# MegaGRRLDesktop.net
KiCad netlist of a schematic drawn in EAGLE
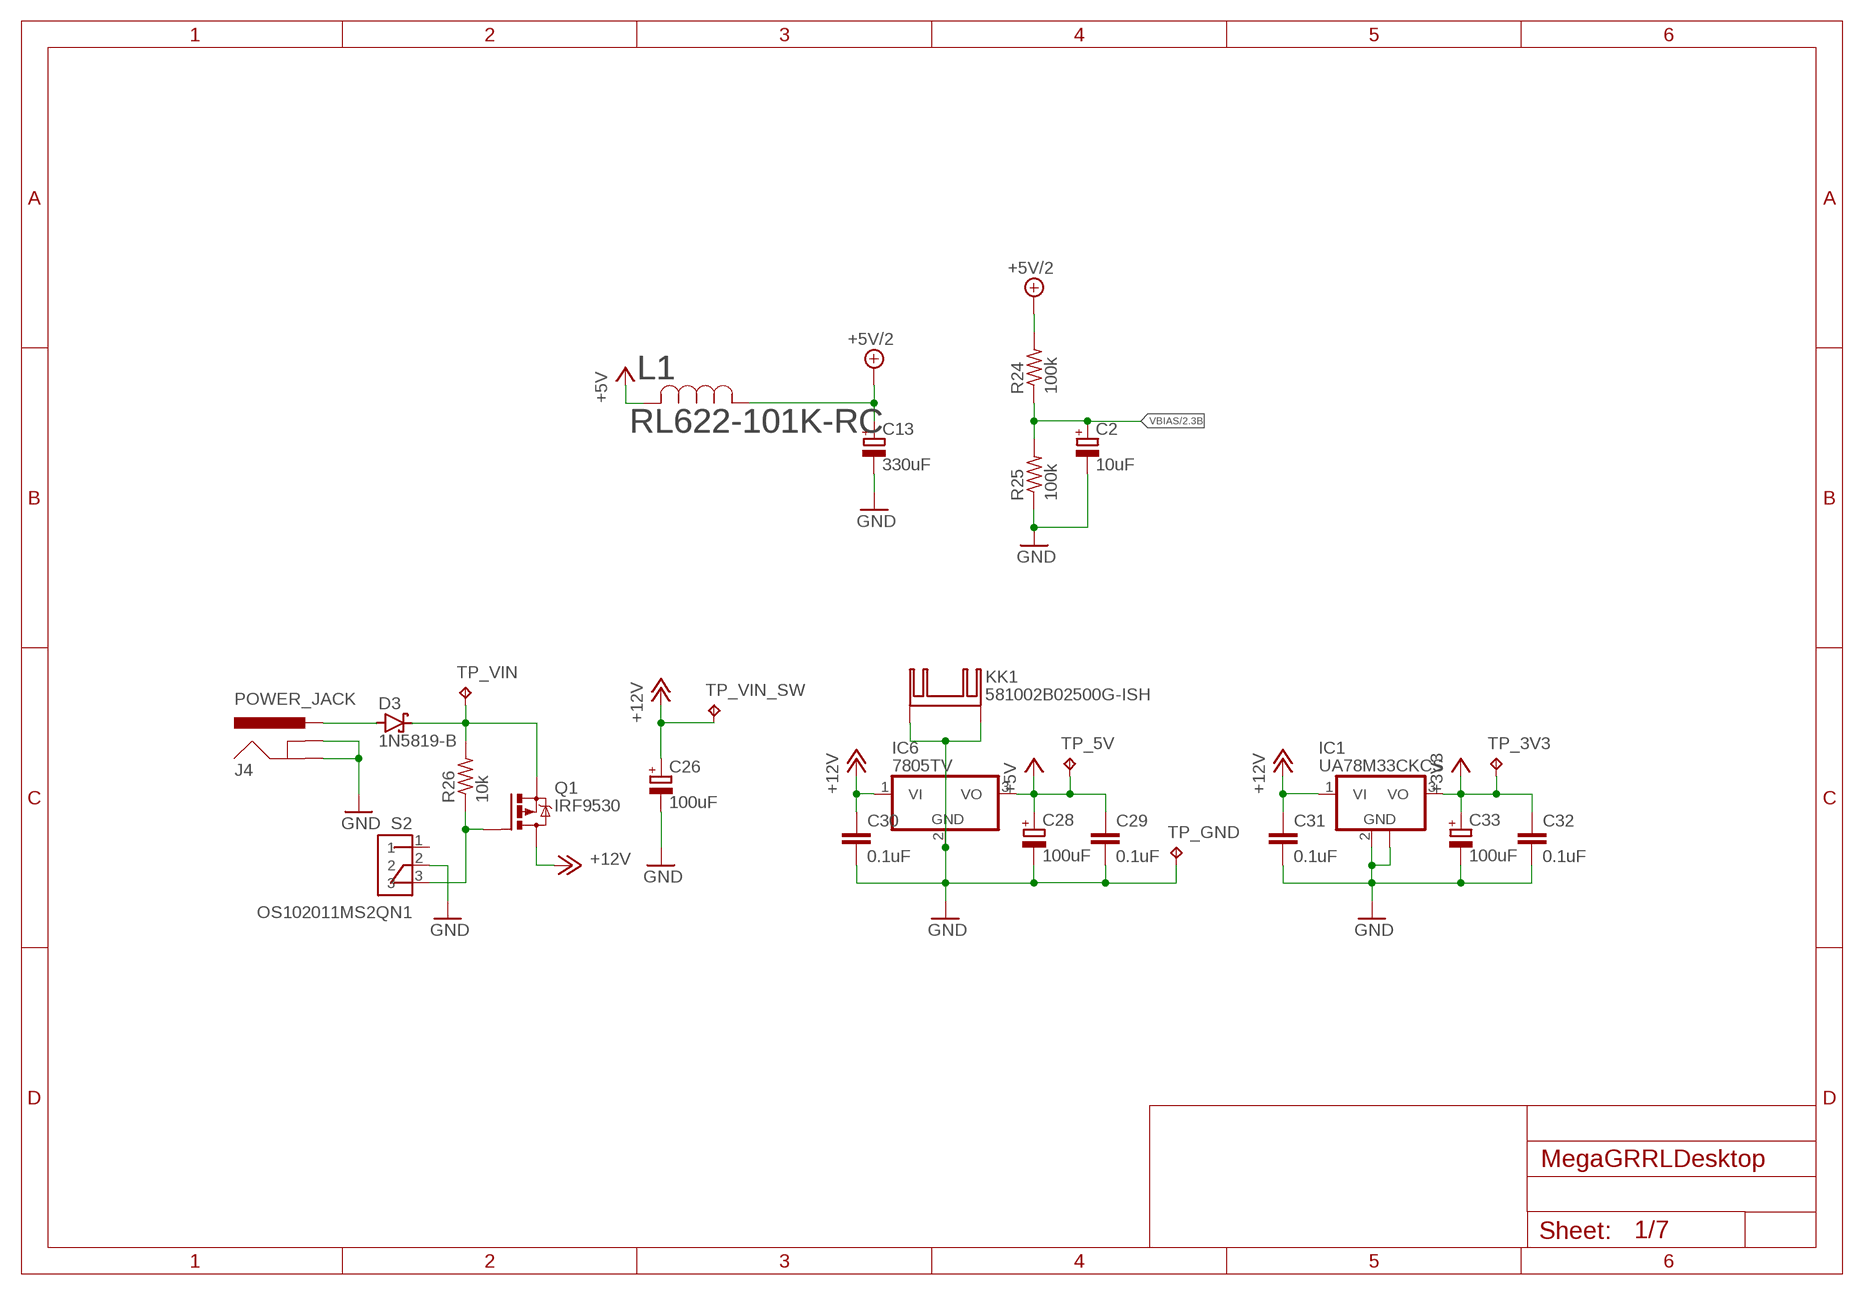
[diagram p0: schematic, sheet 1]
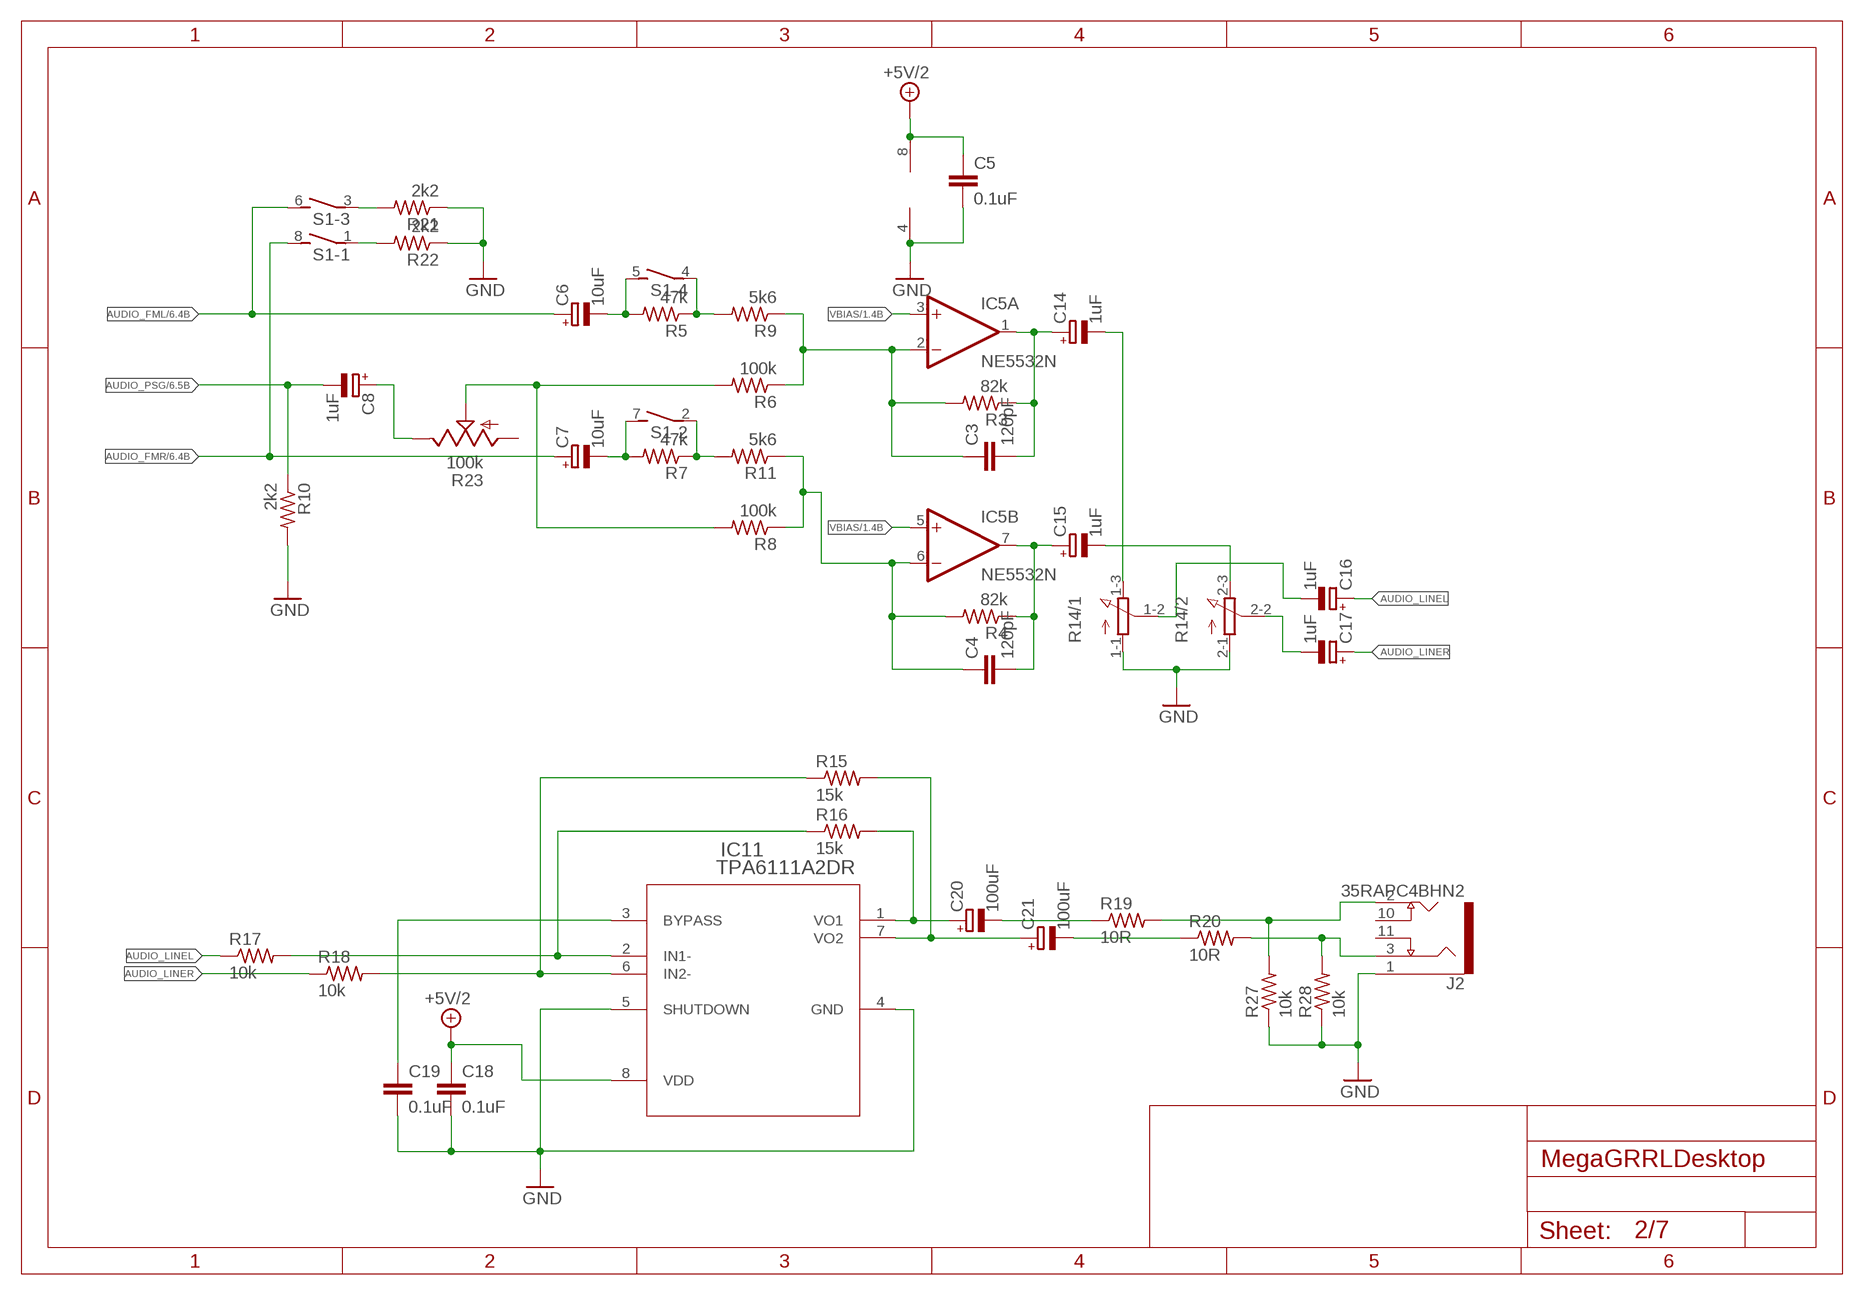
[diagram p1: schematic, sheet 2]
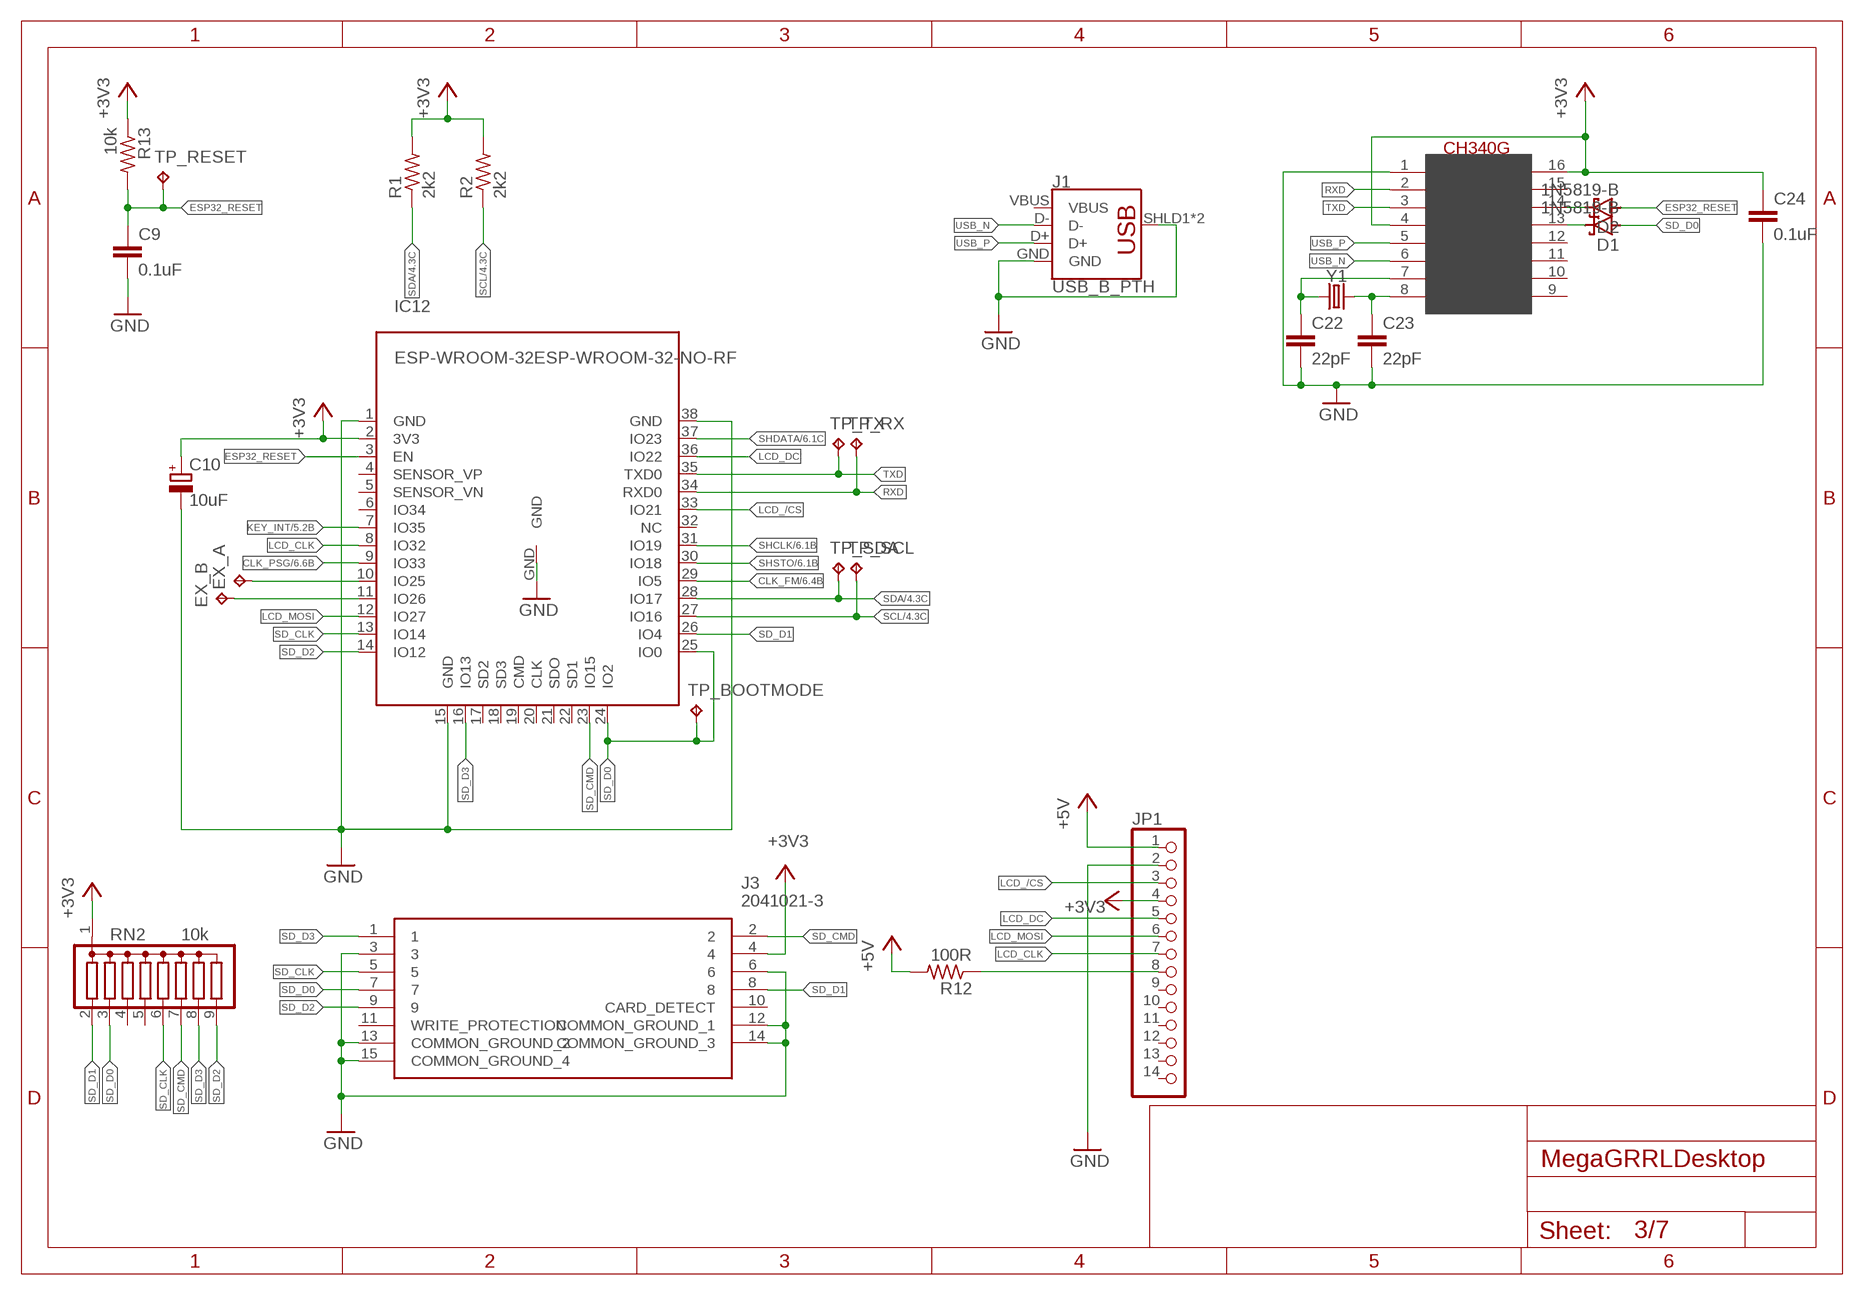
[diagram p2: schematic, sheet 3]
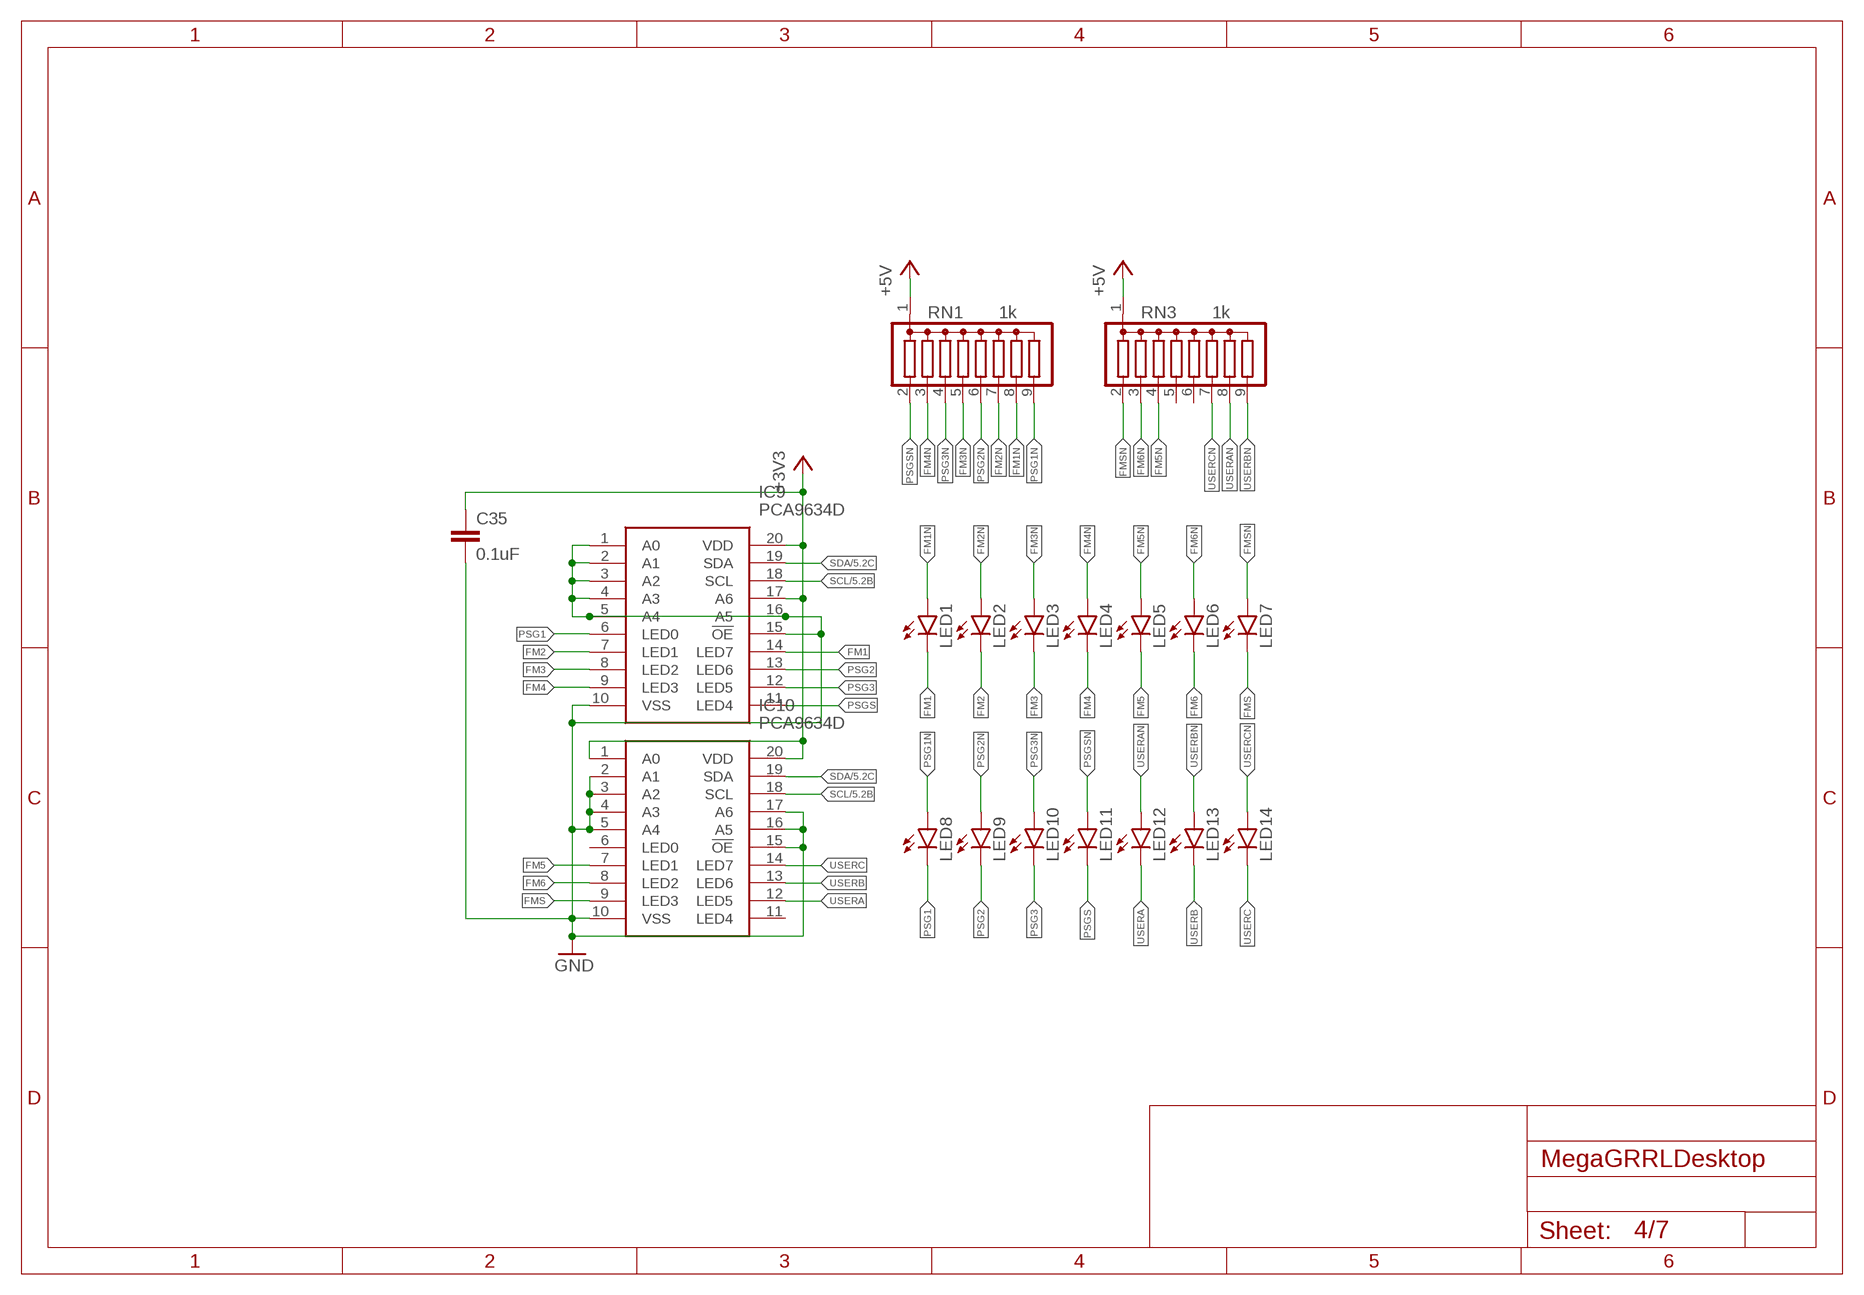
[diagram p3: schematic, sheet 4]
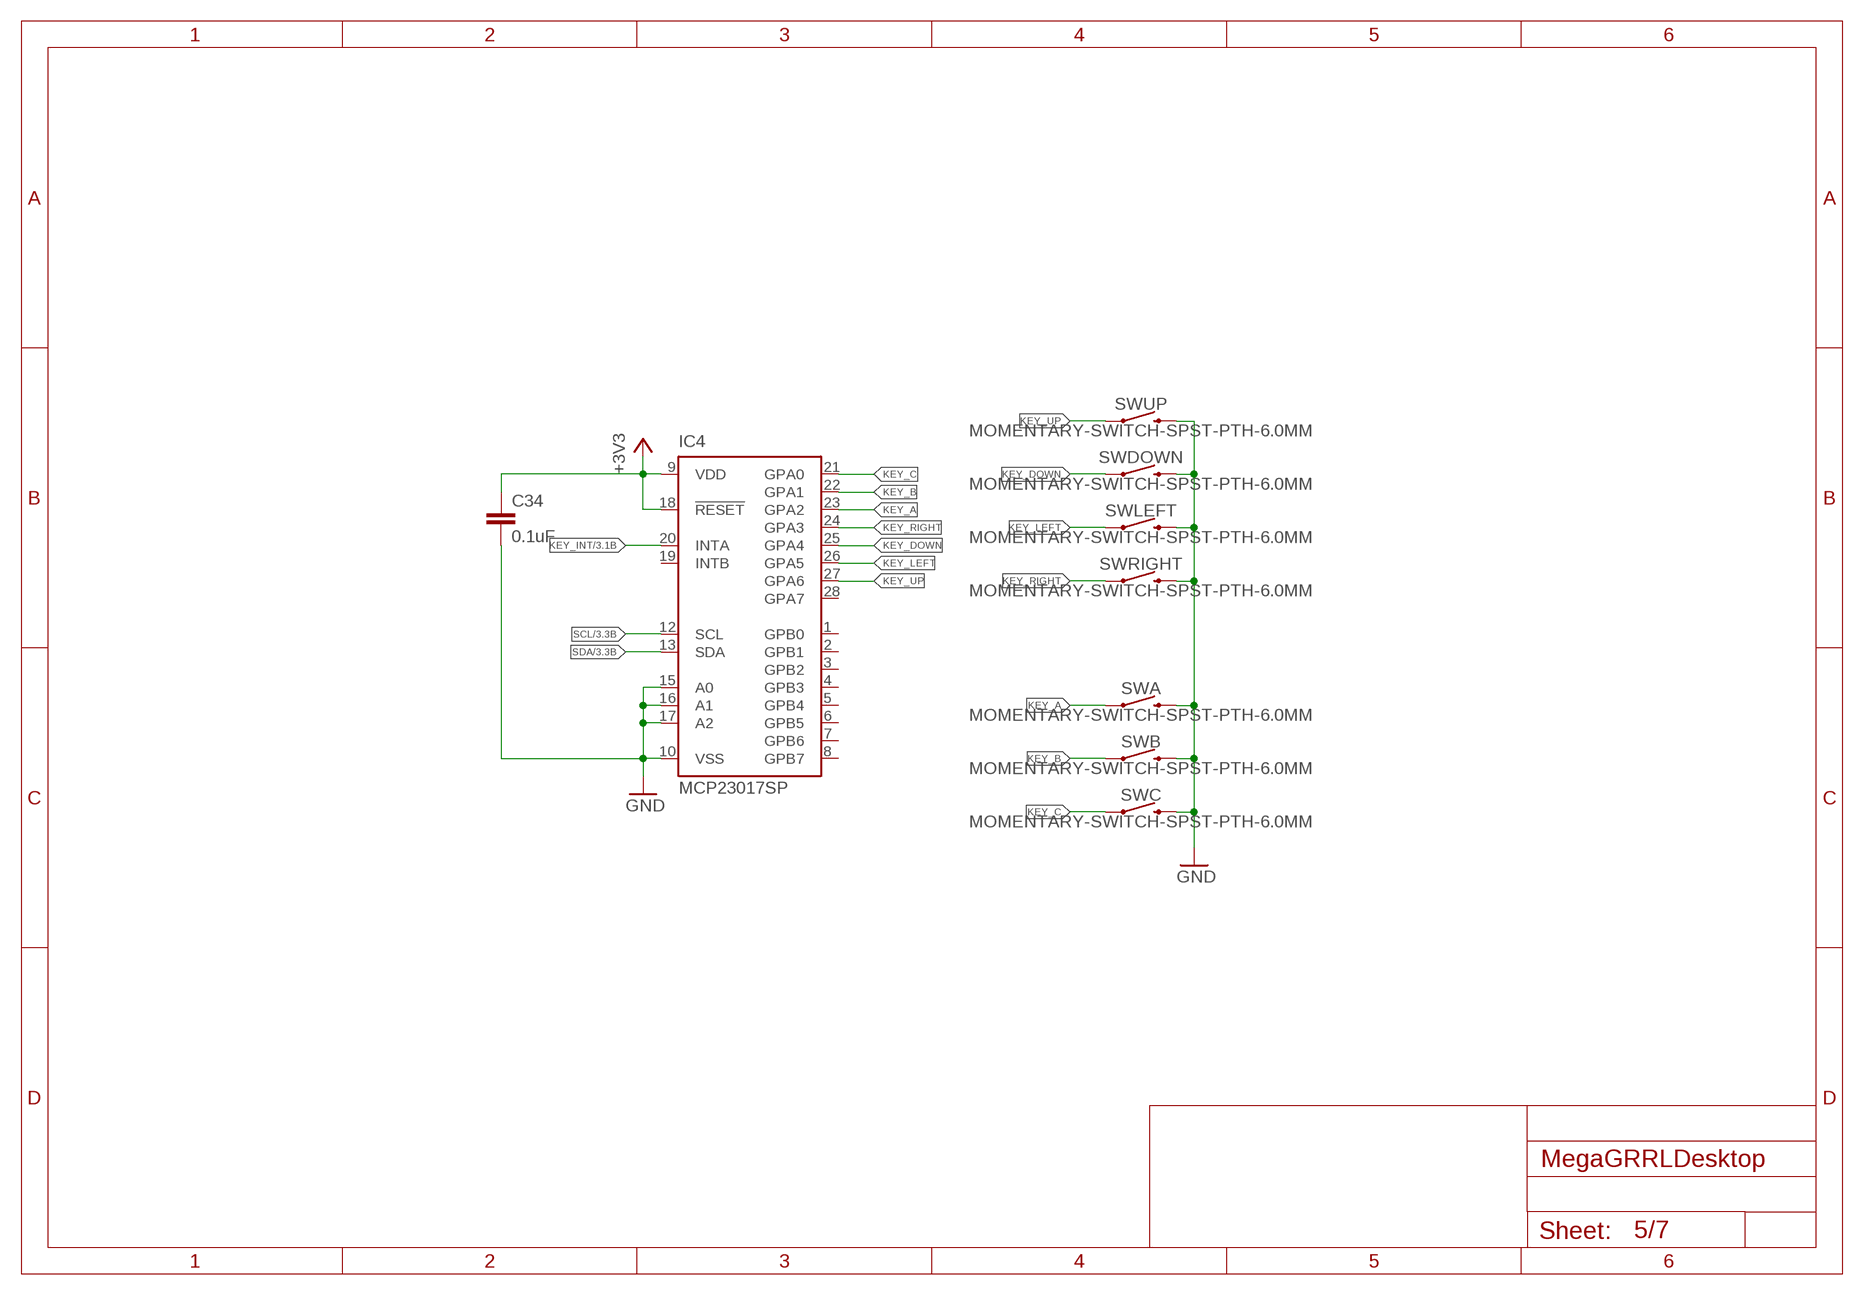
[diagram p4: schematic, sheet 5]
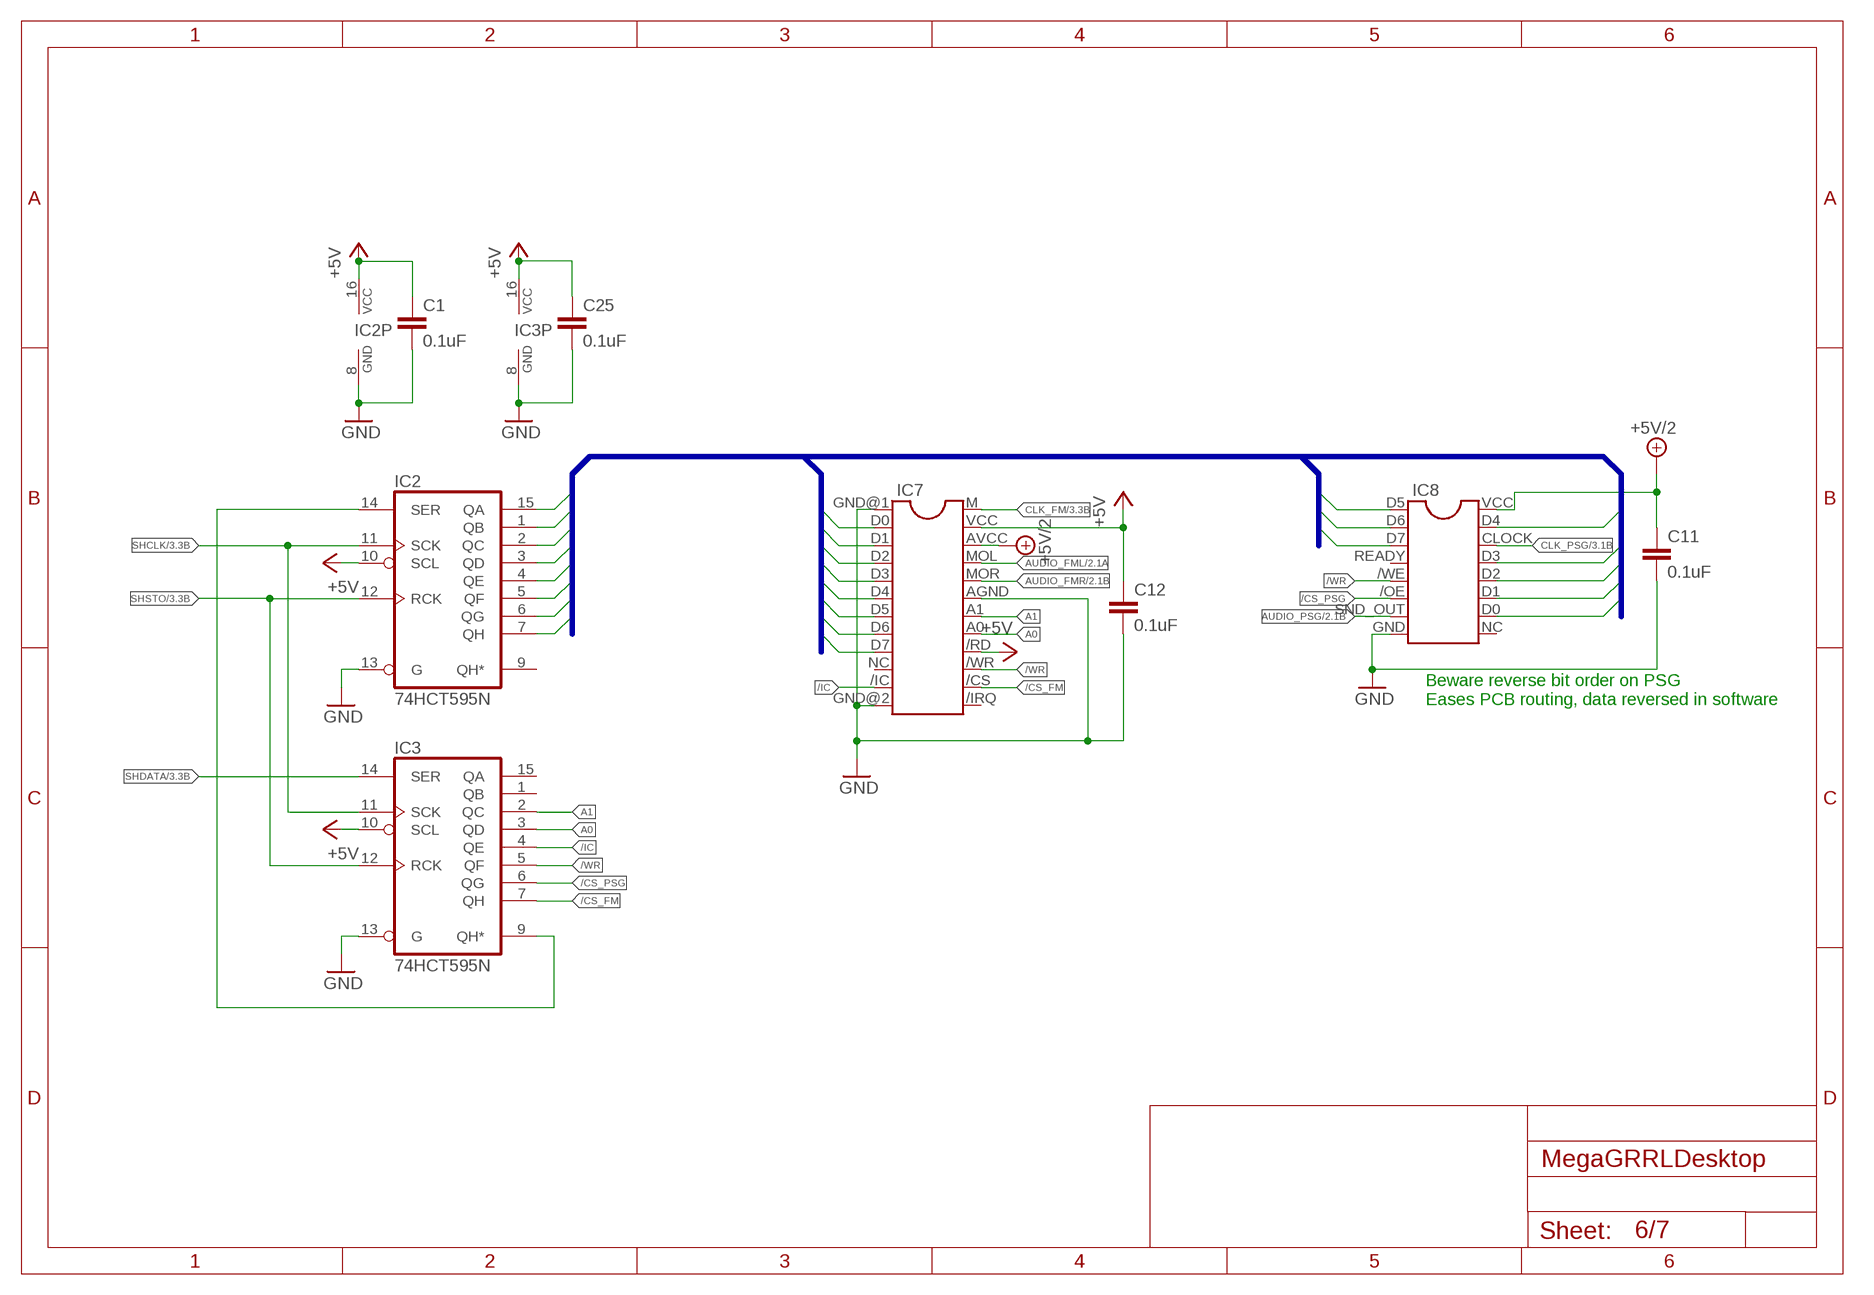
[diagram p5: schematic, sheet 6]
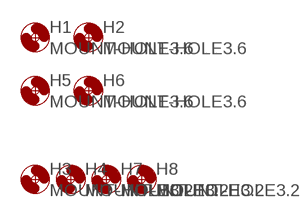
[diagram p6: schematic, sheet 7]

(export (version "E")
  (design (tool "Eeschema 10.0.6"))
  (components
    (comp (ref "C2")
      (value "10uF")
      (footprint "eagle-import:E2,5-5")
      (libsource (lib "eagle-import") (part "CPOL-EUE2.5-5"))
    )
    (comp (ref "C13")
      (value "330uF")
      (footprint "eagle-import:E2,5-7")
      (libsource (lib "eagle-import") (part "CPOL-EUE2.5-7"))
    )
    (comp (ref "C26")
      (value "100uF")
      (footprint "eagle-import:E2,5-7")
      (libsource (lib "eagle-import") (part "CPOL-EUE2.5-7"))
    )
    (comp (ref "C28")
      (value "100uF")
      (footprint "eagle-import:E2,5-7")
      (libsource (lib "eagle-import") (part "CPOL-EUE2.5-7"))
    )
    (comp (ref "C29")
      (value "0.1uF")
      (footprint "eagle-import:C025-024X044")
      (libsource (lib "eagle-import") (part "C-EU025-024X044"))
    )
    (comp (ref "C30")
      (value "0.1uF")
      (footprint "eagle-import:C025-024X044")
      (libsource (lib "eagle-import") (part "C-EU025-024X044"))
    )
    (comp (ref "C31")
      (value "0.1uF")
      (footprint "eagle-import:C025-024X044")
      (libsource (lib "eagle-import") (part "C-EU025-024X044"))
    )
    (comp (ref "C32")
      (value "0.1uF")
      (footprint "eagle-import:C025-024X044")
      (libsource (lib "eagle-import") (part "C-EU025-024X044"))
    )
    (comp (ref "C33")
      (value "100uF")
      (footprint "eagle-import:E2,5-7")
      (libsource (lib "eagle-import") (part "CPOL-EUE2.5-7"))
    )
    (comp (ref "D3")
      (value "1N5819-B")
      (footprint "eagle-import:DO41-7.6")
      (libsource (lib "eagle-import") (part "1N5819-B"))
    )
    (comp (ref "IC1")
      (value "UA78M33CKCS")
      (footprint "eagle-import:TO220H")
      (libsource (lib "eagle-import") (part "UA78MKCS33"))
    )
    (comp (ref "IC6")
      (value "7805TV")
      (footprint "eagle-import:TO220V")
      (libsource (lib "eagle-import") (part "78TV05"))
    )
    (comp (ref "J4")
      (value "POWER_JACK")
      (footprint "eagle-import:POWER_JACK_PTH")
      (libsource (lib "eagle-import") (part "POWER_JACK"))
    )
    (comp (ref "KK1")
      (value "581002B02500G-ISH")
      (footprint "eagle-import:581002B02500G-ISH")
      (libsource (lib "eagle-import") (part "581002B02500G-ISH"))
    )
    (comp (ref "L1")
      (value "RL622-101K-RC")
      (footprint "eagle-import:RL622_SERIES")
      (fields (field (name "MANUFACTURER_PART_NUMBER") "RL622101KRC"))
      (libsource (lib "eagle-import") (part "RL622-101K-RC"))
    )
    (comp (ref "Q1")
      (value "IRF9530")
      (footprint "eagle-import:TO220BV")
      (libsource (lib "eagle-import") (part "IRF9530"))
    )
    (comp (ref "R24")
      (value "100k")
      (footprint "eagle-import:0204_7")
      (libsource (lib "eagle-import") (part "R-US_0204/7"))
    )
    (comp (ref "R25")
      (value "100k")
      (footprint "eagle-import:0204_7")
      (libsource (lib "eagle-import") (part "R-US_0204/7"))
    )
    (comp (ref "R26")
      (value "10k")
      (footprint "eagle-import:0204_7")
      (libsource (lib "eagle-import") (part "R-US_0204/7"))
    )
    (comp (ref "S2")
      (value "OS102011MS2QN1")
      (footprint "eagle-import:SW_OS102011MS2QN1")
      (fields (field (name "DIGI-KEY_PART_NUMBER") "CKN9565-ND") (field (name "MF") "C&K"))
      (libsource (lib "eagle-import") (part "OS102011MS2QN1"))
    )
    (comp (ref "TP_3V3")
      (value "TPB1,27")
      (footprint "eagle-import:B1,27")
      (fields (field (name "SPICEPREFIX") "X"))
      (libsource (lib "eagle-import") (part "TPB1,27"))
    )
    (comp (ref "TP_5V")
      (value "TPB1,27")
      (footprint "eagle-import:B1,27")
      (fields (field (name "SPICEPREFIX") "X"))
      (libsource (lib "eagle-import") (part "TPB1,27"))
    )
    (comp (ref "TP_GND")
      (value "TPB1,27")
      (footprint "eagle-import:B1,27")
      (fields (field (name "SPICEPREFIX") "X"))
      (libsource (lib "eagle-import") (part "TPB1,27"))
    )
    (comp (ref "TP_VIN")
      (value "TPB1,27")
      (footprint "eagle-import:B1,27")
      (fields (field (name "SPICEPREFIX") "X"))
      (libsource (lib "eagle-import") (part "TPB1,27"))
    )
    (comp (ref "TP_VIN_SW")
      (value "TPB1,27")
      (footprint "eagle-import:B1,27")
      (fields (field (name "SPICEPREFIX") "X"))
      (libsource (lib "eagle-import") (part "TPB1,27"))
    )
    (comp (ref "C3")
      (value "120pF")
      (footprint "eagle-import:C025-024X044")
      (libsource (lib "eagle-import") (part "C-EU025-024X044"))
    )
    (comp (ref "C4")
      (value "120pF")
      (footprint "eagle-import:C025-024X044")
      (libsource (lib "eagle-import") (part "C-EU025-024X044"))
    )
    (comp (ref "C5")
      (value "0.1uF")
      (footprint "eagle-import:C025-024X044")
      (libsource (lib "eagle-import") (part "C-EU025-024X044"))
    )
    (comp (ref "C6")
      (value "10uF")
      (footprint "eagle-import:E2,5-5")
      (libsource (lib "eagle-import") (part "CPOL-EUE2.5-5"))
    )
    (comp (ref "C7")
      (value "10uF")
      (footprint "eagle-import:E2,5-5")
      (libsource (lib "eagle-import") (part "CPOL-EUE2.5-5"))
    )
    (comp (ref "C8")
      (value "1uF")
      (footprint "eagle-import:E2-4")
      (libsource (lib "eagle-import") (part "CPOL-EUE2-4"))
    )
    (comp (ref "C14")
      (value "1uF")
      (footprint "eagle-import:E2-4")
      (libsource (lib "eagle-import") (part "CPOL-EUE2-4"))
    )
    (comp (ref "C15")
      (value "1uF")
      (footprint "eagle-import:E2-4")
      (libsource (lib "eagle-import") (part "CPOL-EUE2-4"))
    )
    (comp (ref "C16")
      (value "1uF")
      (footprint "eagle-import:E2-4")
      (libsource (lib "eagle-import") (part "CPOL-EUE2-4"))
    )
    (comp (ref "C17")
      (value "1uF")
      (footprint "eagle-import:E2-4")
      (libsource (lib "eagle-import") (part "CPOL-EUE2-4"))
    )
    (comp (ref "C18")
      (value "0.1uF")
      (footprint "eagle-import:C025-024X044")
      (libsource (lib "eagle-import") (part "C-EU025-024X044"))
    )
    (comp (ref "C19")
      (value "0.1uF")
      (footprint "eagle-import:C025-024X044")
      (libsource (lib "eagle-import") (part "C-EU025-024X044"))
    )
    (comp (ref "C20")
      (value "100uF")
      (footprint "eagle-import:E2,5-7")
      (libsource (lib "eagle-import") (part "CPOL-EUE2.5-7"))
    )
    (comp (ref "C21")
      (value "100uF")
      (footprint "eagle-import:E2,5-7")
      (libsource (lib "eagle-import") (part "CPOL-EUE2.5-7"))
    )
    (comp (ref "IC5")
      (value "NE5532N")
      (footprint "eagle-import:DIL08")
      (libsource (lib "eagle-import") (part "NE5532N"))
    )
    (comp (ref "IC11")
      (value "TPA6111A2DR")
      (footprint "eagle-import:D8")
      (libsource (lib "eagle-import") (part "TPA6111A2DR"))
    )
    (comp (ref "J2")
      (value "35RAPC4BHN2")
      (footprint "eagle-import:SWITCHCRAFT_35RAPC4BHN2")
      (fields (field (name "DIGI-KEY_PART_NUMBER") "SC1459-ND") (field (name "MF") "Switchcraft"))
      (libsource (lib "eagle-import") (part "35RAPC4BHN2"))
    )
    (comp (ref "R3")
      (value "82k")
      (footprint "eagle-import:0204_7")
      (libsource (lib "eagle-import") (part "R-US_0204/7"))
    )
    (comp (ref "R4")
      (value "82k")
      (footprint "eagle-import:0204_7")
      (libsource (lib "eagle-import") (part "R-US_0204/7"))
    )
    (comp (ref "R5")
      (value "47k")
      (footprint "eagle-import:0204_7")
      (libsource (lib "eagle-import") (part "R-US_0204/7"))
    )
    (comp (ref "R6")
      (value "100k")
      (footprint "eagle-import:0204_7")
      (libsource (lib "eagle-import") (part "R-US_0204/7"))
    )
    (comp (ref "R7")
      (value "47k")
      (footprint "eagle-import:0204_7")
      (libsource (lib "eagle-import") (part "R-US_0204/7"))
    )
    (comp (ref "R8")
      (value "100k")
      (footprint "eagle-import:0204_7")
      (libsource (lib "eagle-import") (part "R-US_0204/7"))
    )
    (comp (ref "R9")
      (value "5k6")
      (footprint "eagle-import:0204_7")
      (libsource (lib "eagle-import") (part "R-US_0204/7"))
    )
    (comp (ref "R10")
      (value "2k2")
      (footprint "eagle-import:0204_7")
      (libsource (lib "eagle-import") (part "R-US_0204/7"))
    )
    (comp (ref "R11")
      (value "5k6")
      (footprint "eagle-import:0204_7")
      (libsource (lib "eagle-import") (part "R-US_0204/7"))
    )
    (comp (ref "R14")
      (value "3RP/1610G")
      (footprint "eagle-import:3RP_1610G")
      (libsource (lib "eagle-import") (part "3RP/1610G"))
    )
    (comp (ref "R15")
      (value "15k")
      (footprint "eagle-import:0204_7")
      (libsource (lib "eagle-import") (part "R-US_0204/7"))
    )
    (comp (ref "R16")
      (value "15k")
      (footprint "eagle-import:0204_7")
      (libsource (lib "eagle-import") (part "R-US_0204/7"))
    )
    (comp (ref "R17")
      (value "10k")
      (footprint "eagle-import:0204_7")
      (libsource (lib "eagle-import") (part "R-US_0204/7"))
    )
    (comp (ref "R18")
      (value "10k")
      (footprint "eagle-import:0204_7")
      (libsource (lib "eagle-import") (part "R-US_0204/7"))
    )
    (comp (ref "R19")
      (value "10R")
      (footprint "eagle-import:0204_7")
      (libsource (lib "eagle-import") (part "R-US_0204/7"))
    )
    (comp (ref "R20")
      (value "10R")
      (footprint "eagle-import:0204_7")
      (libsource (lib "eagle-import") (part "R-US_0204/7"))
    )
    (comp (ref "R21")
      (value "2k2")
      (footprint "eagle-import:0204_7")
      (libsource (lib "eagle-import") (part "R-US_0204/7"))
    )
    (comp (ref "R22")
      (value "2k2")
      (footprint "eagle-import:0204_7")
      (libsource (lib "eagle-import") (part "R-US_0204/7"))
    )
    (comp (ref "R23")
      (value "100k")
      (footprint "eagle-import:S64W")
      (libsource (lib "eagle-import") (part "TRIM_US-S64W"))
    )
    (comp (ref "R27")
      (value "10k")
      (footprint "eagle-import:0204_7")
      (libsource (lib "eagle-import") (part "R-US_0204/7"))
    )
    (comp (ref "R28")
      (value "10k")
      (footprint "eagle-import:0204_7")
      (libsource (lib "eagle-import") (part "R-US_0204/7"))
    )
    (comp (ref "S1")
      (value "DIP04S")
      (footprint "eagle-import:DIP04S")
      (libsource (lib "eagle-import") (part "DIP04S"))
    )
    (comp (ref "C1")
      (value "0.1uF")
      (footprint "eagle-import:C025-024X044")
      (libsource (lib "eagle-import") (part "C-EU025-024X044"))
    )
    (comp (ref "C11")
      (value "0.1uF")
      (footprint "eagle-import:C025-024X044")
      (libsource (lib "eagle-import") (part "C-EU025-024X044"))
    )
    (comp (ref "C12")
      (value "0.1uF")
      (footprint "eagle-import:C025-024X044")
      (libsource (lib "eagle-import") (part "C-EU025-024X044"))
    )
    (comp (ref "C25")
      (value "0.1uF")
      (footprint "eagle-import:C025-024X044")
      (libsource (lib "eagle-import") (part "C-EU025-024X044"))
    )
    (comp (ref "IC2")
      (value "74HCT595N")
      (footprint "eagle-import:DIL16")
      (libsource (lib "eagle-import") (part "74595NHCT"))
    )
    (comp (ref "IC3")
      (value "74HCT595N")
      (footprint "eagle-import:DIL16")
      (libsource (lib "eagle-import") (part "74595NHCT"))
    )
    (comp (ref "IC7")
      (value "YM2612")
      (footprint "eagle-import:YM2612")
      (libsource (lib "eagle-import") (part "YM2612"))
    )
    (comp (ref "IC8")
      (value "SN76489")
      (footprint "eagle-import:SN76489")
      (libsource (lib "eagle-import") (part "SN76489"))
    )
    (comp (ref "C9")
      (value "0.1uF")
      (footprint "eagle-import:C025-024X044")
      (libsource (lib "eagle-import") (part "C-EU025-024X044"))
    )
    (comp (ref "C10")
      (value "10uF")
      (footprint "eagle-import:E2,5-5")
      (libsource (lib "eagle-import") (part "CPOL-EUE2.5-5"))
    )
    (comp (ref "C22")
      (value "22pF")
      (footprint "eagle-import:C025-024X044")
      (libsource (lib "eagle-import") (part "C-EU025-024X044"))
    )
    (comp (ref "C23")
      (value "22pF")
      (footprint "eagle-import:C025-024X044")
      (libsource (lib "eagle-import") (part "C-EU025-024X044"))
    )
    (comp (ref "C24")
      (value "0.1uF")
      (footprint "eagle-import:C025-024X044")
      (libsource (lib "eagle-import") (part "C-EU025-024X044"))
    )
    (comp (ref "D1")
      (value "1N5819-B")
      (footprint "eagle-import:DO41-7.6")
      (libsource (lib "eagle-import") (part "1N5819-B"))
    )
    (comp (ref "D2")
      (value "1N5819-B")
      (footprint "eagle-import:DO41-7.6")
      (libsource (lib "eagle-import") (part "1N5819-B"))
    )
    (comp (ref "EX_A")
      (value "TPB1,27")
      (footprint "eagle-import:B1,27")
      (fields (field (name "SPICEPREFIX") "X"))
      (libsource (lib "eagle-import") (part "TPB1,27"))
    )
    (comp (ref "EX_B")
      (value "TPB1,27")
      (footprint "eagle-import:B1,27")
      (fields (field (name "SPICEPREFIX") "X"))
      (libsource (lib "eagle-import") (part "TPB1,27"))
    )
    (comp (ref "IC12")
      (value "ESP-WROOM-32ESP-WROOM-32-NO-RF")
      (footprint "eagle-import:ESP-WROOM-32-NO-RF")
      (libsource (lib "eagle-import") (part "ESP-WROOM-32ESP-WROOM-32-NO-RF"))
    )
    (comp (ref "IC14")
      (value "CH340G")
      (footprint "eagle-import:SOIC16")
      (libsource (lib "eagle-import") (part "CH340G"))
    )
    (comp (ref "J1")
      (value "USB_B_PTH")
      (footprint "eagle-import:USB-B-PTH")
      (libsource (lib "eagle-import") (part "USB_B_PTH"))
    )
    (comp (ref "J3")
      (value "2041021-3")
      (footprint "eagle-import:2041021-3_2")
      (fields (field (name "MOUSER_PART_NUMBER") "571-2041021-3"))
      (libsource (lib "eagle-import") (part "2041021-3"))
    )
    (comp (ref "JP1")
      (value "ILI9341_2_4")
      (footprint "eagle-import:ILI9341_2_4")
      (libsource (lib "eagle-import") (part "ILI9341_2_4"))
    )
    (comp (ref "R1")
      (value "2k2")
      (footprint "eagle-import:0204_7")
      (libsource (lib "eagle-import") (part "R-US_0204/7"))
    )
    (comp (ref "R2")
      (value "2k2")
      (footprint "eagle-import:0204_7")
      (libsource (lib "eagle-import") (part "R-US_0204/7"))
    )
    (comp (ref "R12")
      (value "100R")
      (footprint "eagle-import:0204_7")
      (libsource (lib "eagle-import") (part "R-US_0204/7"))
    )
    (comp (ref "R13")
      (value "10k")
      (footprint "eagle-import:0204_7")
      (libsource (lib "eagle-import") (part "R-US_0204/7"))
    )
    (comp (ref "RN2")
      (value "10k")
      (footprint "eagle-import:SIL9")
      (libsource (lib "eagle-import") (part "G08R"))
    )
    (comp (ref "TP_BOOTMODE")
      (value "TPB1,27")
      (footprint "eagle-import:B1,27")
      (fields (field (name "SPICEPREFIX") "X"))
      (libsource (lib "eagle-import") (part "TPB1,27"))
    )
    (comp (ref "TP_RESET")
      (value "TPB1,27")
      (footprint "eagle-import:B1,27")
      (fields (field (name "SPICEPREFIX") "X"))
      (libsource (lib "eagle-import") (part "TPB1,27"))
    )
    (comp (ref "TP_RX")
      (value "TPB1,27")
      (footprint "eagle-import:B1,27")
      (fields (field (name "SPICEPREFIX") "X"))
      (libsource (lib "eagle-import") (part "TPB1,27"))
    )
    (comp (ref "TP_SCL")
      (value "TPB1,27")
      (footprint "eagle-import:B1,27")
      (fields (field (name "SPICEPREFIX") "X"))
      (libsource (lib "eagle-import") (part "TPB1,27"))
    )
    (comp (ref "TP_SDA")
      (value "TPB1,27")
      (footprint "eagle-import:B1,27")
      (fields (field (name "SPICEPREFIX") "X"))
      (libsource (lib "eagle-import") (part "TPB1,27"))
    )
    (comp (ref "TP_TX")
      (value "TPB1,27")
      (footprint "eagle-import:B1,27")
      (fields (field (name "SPICEPREFIX") "X"))
      (libsource (lib "eagle-import") (part "TPB1,27"))
    )
    (comp (ref "Y1")
      (value "CRYSTALPTH-HC49US")
      (footprint "eagle-import:HC49US")
      (libsource (lib "eagle-import") (part "CRYSTALPTH-HC49US"))
    )
    (comp (ref "H1")
      (value "MOUNT-HOLE3.6")
      (footprint "eagle-import:3,6")
      (libsource (lib "eagle-import") (part "MOUNT-HOLE3.6"))
    )
    (comp (ref "H2")
      (value "MOUNT-HOLE3.6")
      (footprint "eagle-import:3,6")
      (libsource (lib "eagle-import") (part "MOUNT-HOLE3.6"))
    )
    (comp (ref "H3")
      (value "MOUNT-HOLE3.2")
      (footprint "eagle-import:3,2")
      (libsource (lib "eagle-import") (part "MOUNT-HOLE3.2"))
    )
    (comp (ref "H4")
      (value "MOUNT-HOLE3.2")
      (footprint "eagle-import:3,2")
      (libsource (lib "eagle-import") (part "MOUNT-HOLE3.2"))
    )
    (comp (ref "H5")
      (value "MOUNT-HOLE3.6")
      (footprint "eagle-import:3,6")
      (libsource (lib "eagle-import") (part "MOUNT-HOLE3.6"))
    )
    (comp (ref "H6")
      (value "MOUNT-HOLE3.6")
      (footprint "eagle-import:3,6")
      (libsource (lib "eagle-import") (part "MOUNT-HOLE3.6"))
    )
    (comp (ref "H7")
      (value "MOUNT-HOLE3.2")
      (footprint "eagle-import:3,2")
      (libsource (lib "eagle-import") (part "MOUNT-HOLE3.2"))
    )
    (comp (ref "H8")
      (value "MOUNT-HOLE3.2")
      (footprint "eagle-import:3,2")
      (libsource (lib "eagle-import") (part "MOUNT-HOLE3.2"))
    )
    (comp (ref "C34")
      (value "0.1uF")
      (footprint "eagle-import:C025-024X044")
      (libsource (lib "eagle-import") (part "C-EU025-024X044"))
    )
    (comp (ref "IC4")
      (value "MCP23017SP")
      (footprint "eagle-import:DIL28-3")
      (fields (field (name "MF") "MICROCHIP") (field (name "MPN") "MCP23017-E/SP"))
      (libsource (lib "eagle-import") (part "MCP23017SP"))
    )
    (comp (ref "SWA")
      (value "MOMENTARY-SWITCH-SPST-PTH-6.0MM")
      (footprint "eagle-import:TACTILE_SWITCH_PTH_6.0MM")
      (libsource (lib "eagle-import") (part "MOMENTARY-SWITCH-SPST-PTH-6.0MM"))
    )
    (comp (ref "SWB")
      (value "MOMENTARY-SWITCH-SPST-PTH-6.0MM")
      (footprint "eagle-import:TACTILE_SWITCH_PTH_6.0MM")
      (libsource (lib "eagle-import") (part "MOMENTARY-SWITCH-SPST-PTH-6.0MM"))
    )
    (comp (ref "SWC")
      (value "MOMENTARY-SWITCH-SPST-PTH-6.0MM")
      (footprint "eagle-import:TACTILE_SWITCH_PTH_6.0MM")
      (libsource (lib "eagle-import") (part "MOMENTARY-SWITCH-SPST-PTH-6.0MM"))
    )
    (comp (ref "SWDOWN")
      (value "MOMENTARY-SWITCH-SPST-PTH-6.0MM")
      (footprint "eagle-import:TACTILE_SWITCH_PTH_6.0MM")
      (libsource (lib "eagle-import") (part "MOMENTARY-SWITCH-SPST-PTH-6.0MM"))
    )
    (comp (ref "SWLEFT")
      (value "MOMENTARY-SWITCH-SPST-PTH-6.0MM")
      (footprint "eagle-import:TACTILE_SWITCH_PTH_6.0MM")
      (libsource (lib "eagle-import") (part "MOMENTARY-SWITCH-SPST-PTH-6.0MM"))
    )
    (comp (ref "SWRIGHT")
      (value "MOMENTARY-SWITCH-SPST-PTH-6.0MM")
      (footprint "eagle-import:TACTILE_SWITCH_PTH_6.0MM")
      (libsource (lib "eagle-import") (part "MOMENTARY-SWITCH-SPST-PTH-6.0MM"))
    )
    (comp (ref "SWUP")
      (value "MOMENTARY-SWITCH-SPST-PTH-6.0MM")
      (footprint "eagle-import:TACTILE_SWITCH_PTH_6.0MM")
      (libsource (lib "eagle-import") (part "MOMENTARY-SWITCH-SPST-PTH-6.0MM"))
    )
    (comp (ref "C35")
      (value "0.1uF")
      (footprint "eagle-import:C025-024X044")
      (libsource (lib "eagle-import") (part "C-EU025-024X044"))
    )
    (comp (ref "IC9")
      (value "PCA9634D")
      (footprint "eagle-import:SOIC127P1032X265-20N")
      (libsource (lib "eagle-import") (part "PCA9634D"))
    )
    (comp (ref "IC10")
      (value "PCA9634D")
      (footprint "eagle-import:SOIC127P1032X265-20N")
      (libsource (lib "eagle-import") (part "PCA9634D"))
    )
    (comp (ref "LED1")
      (value "LED3MM")
      (footprint "eagle-import:LED3MM")
      (libsource (lib "eagle-import") (part "LED3MM"))
    )
    (comp (ref "LED2")
      (value "LED3MM")
      (footprint "eagle-import:LED3MM")
      (libsource (lib "eagle-import") (part "LED3MM"))
    )
    (comp (ref "LED3")
      (value "LED3MM")
      (footprint "eagle-import:LED3MM")
      (libsource (lib "eagle-import") (part "LED3MM"))
    )
    (comp (ref "LED4")
      (value "LED3MM")
      (footprint "eagle-import:LED3MM")
      (libsource (lib "eagle-import") (part "LED3MM"))
    )
    (comp (ref "LED5")
      (value "LED3MM")
      (footprint "eagle-import:LED3MM")
      (libsource (lib "eagle-import") (part "LED3MM"))
    )
    (comp (ref "LED6")
      (value "LED3MM")
      (footprint "eagle-import:LED3MM")
      (libsource (lib "eagle-import") (part "LED3MM"))
    )
    (comp (ref "LED7")
      (value "LED3MM")
      (footprint "eagle-import:LED3MM")
      (libsource (lib "eagle-import") (part "LED3MM"))
    )
    (comp (ref "LED8")
      (value "LED3MM")
      (footprint "eagle-import:LED3MM")
      (libsource (lib "eagle-import") (part "LED3MM"))
    )
    (comp (ref "LED9")
      (value "LED3MM")
      (footprint "eagle-import:LED3MM")
      (libsource (lib "eagle-import") (part "LED3MM"))
    )
    (comp (ref "LED10")
      (value "LED3MM")
      (footprint "eagle-import:LED3MM")
      (libsource (lib "eagle-import") (part "LED3MM"))
    )
    (comp (ref "LED11")
      (value "LED3MM")
      (footprint "eagle-import:LED3MM")
      (libsource (lib "eagle-import") (part "LED3MM"))
    )
    (comp (ref "LED12")
      (value "LED3MM")
      (footprint "eagle-import:LED3MM")
      (libsource (lib "eagle-import") (part "LED3MM"))
    )
    (comp (ref "LED13")
      (value "LED3MM")
      (footprint "eagle-import:LED3MM")
      (libsource (lib "eagle-import") (part "LED3MM"))
    )
    (comp (ref "LED14")
      (value "LED3MM")
      (footprint "eagle-import:LED3MM")
      (libsource (lib "eagle-import") (part "LED3MM"))
    )
    (comp (ref "RN1")
      (value "1k")
      (footprint "eagle-import:SIL9")
      (libsource (lib "eagle-import") (part "G08R"))
    )
    (comp (ref "RN3")
      (value "1k")
      (footprint "eagle-import:SIL9")
      (libsource (lib "eagle-import") (part "G08R"))
    )
  )
  (nets
    (net (code "1") (name "+3V3") (class "Default")
      (node (ref "C10") (pin "+") (pinfunction "+_+") (pintype "passive"))
      (node (ref "C24") (pin "1") (pinfunction "1_1") (pintype "passive"))
      (node (ref "C32") (pin "1") (pinfunction "1_1") (pintype "passive"))
      (node (ref "C33") (pin "+") (pinfunction "+_+") (pintype "passive"))
      (node (ref "C34") (pin "1") (pinfunction "1_1") (pintype "passive"))
      (node (ref "C35") (pin "1") (pinfunction "1_1") (pintype "passive"))
      (node (ref "IC1") (pin "3") (pinfunction "VO_3") (pintype "passive"))
      (node (ref "IC10") (pin "1") (pinfunction "A0_1") (pintype "bidirectional"))
      (node (ref "IC10") (pin "20") (pinfunction "VDD_20") (pintype "power_in"))
      (node (ref "IC12") (pin "2") (pinfunction "3V3_2") (pintype "bidirectional"))
      (node (ref "IC14") (pin "16") (pinfunction "VCC_16") (pintype "bidirectional"))
      (node (ref "IC14") (pin "4") (pinfunction "V3_4") (pintype "bidirectional"))
      (node (ref "IC4") (pin "18") (pinfunction "~{RESET}_18") (pintype "input"))
      (node (ref "IC4") (pin "9") (pinfunction "VDD_9") (pintype "power_in"))
      (node (ref "IC9") (pin "17") (pinfunction "A6_17") (pintype "bidirectional"))
      (node (ref "IC9") (pin "20") (pinfunction "VDD_20") (pintype "power_in"))
      (node (ref "J3") (pin "4") (pinfunction "4_4") (pintype "bidirectional"))
      (node (ref "JP1") (pin "4") (pinfunction "4_4") (pintype "passive"))
      (node (ref "R1") (pin "2") (pinfunction "2_2") (pintype "passive"))
      (node (ref "R13") (pin "1") (pinfunction "1_1") (pintype "passive"))
      (node (ref "R2") (pin "2") (pinfunction "2_2") (pintype "passive"))
      (node (ref "RN2") (pin "1") (pinfunction "1_1") (pintype "passive"))
      (node (ref "TP_3V3") (pin "TP") (pinfunction "TP_TP") (pintype "input"))
    )
    (net (code "2") (name "+5V") (class "Default")
      (node (ref "C1") (pin "1") (pinfunction "1_1") (pintype "passive"))
      (node (ref "C12") (pin "1") (pinfunction "1_1") (pintype "passive"))
      (node (ref "C25") (pin "1") (pinfunction "1_1") (pintype "passive"))
      (node (ref "C28") (pin "+") (pinfunction "+_+") (pintype "passive"))
      (node (ref "C29") (pin "1") (pinfunction "1_1") (pintype "passive"))
      (node (ref "IC2") (pin "10") (pinfunction "SCL_10") (pintype "input"))
      (node (ref "IC2") (pin "16") (pinfunction "VCC_16") (pintype "power_in"))
      (node (ref "IC3") (pin "10") (pinfunction "SCL_10") (pintype "input"))
      (node (ref "IC3") (pin "16") (pinfunction "VCC_16") (pintype "power_in"))
      (node (ref "IC6") (pin "3") (pinfunction "VO_3") (pintype "passive"))
      (node (ref "IC7") (pin "/RD") (pinfunction "/RD_/RD") (pintype "passive"))
      (node (ref "IC7") (pin "VCC") (pinfunction "VCC_VCC") (pintype "passive"))
      (node (ref "JP1") (pin "1") (pinfunction "1_1") (pintype "passive"))
      (node (ref "L1") (pin "2") (pinfunction "2_2") (pintype "passive"))
      (node (ref "R12") (pin "2") (pinfunction "2_2") (pintype "passive"))
      (node (ref "RN1") (pin "1") (pinfunction "1_1") (pintype "passive"))
      (node (ref "RN3") (pin "1") (pinfunction "1_1") (pintype "passive"))
      (node (ref "TP_5V") (pin "TP") (pinfunction "TP_TP") (pintype "input"))
    )
    (net (code "3") (name "+5V{slash}2") (class "Default")
      (node (ref "C11") (pin "1") (pinfunction "1_1") (pintype "passive"))
      (node (ref "C13") (pin "+") (pinfunction "+_+") (pintype "passive"))
      (node (ref "C18") (pin "1") (pinfunction "1_1") (pintype "passive"))
      (node (ref "C5") (pin "1") (pinfunction "1_1") (pintype "passive"))
      (node (ref "IC11") (pin "8") (pinfunction "VDD_8") (pintype "power_in"))
      (node (ref "IC5") (pin "8") (pinfunction "V+_8") (pintype "power_in"))
      (node (ref "IC7") (pin "AVCC") (pinfunction "AVCC_AVCC") (pintype "passive"))
      (node (ref "IC8") (pin "VCC") (pinfunction "VCC_VCC") (pintype "passive"))
      (node (ref "L1") (pin "1") (pinfunction "1_1") (pintype "passive"))
      (node (ref "R24") (pin "2") (pinfunction "2_2") (pintype "passive"))
    )
    (net (code "4") (name "+12V") (class "Default")
      (node (ref "C26") (pin "+") (pinfunction "+_+") (pintype "passive"))
      (node (ref "C30") (pin "1") (pinfunction "1_1") (pintype "passive"))
      (node (ref "C31") (pin "1") (pinfunction "1_1") (pintype "passive"))
      (node (ref "IC1") (pin "1") (pinfunction "VI_1") (pintype "input"))
      (node (ref "IC6") (pin "1") (pinfunction "VI_1") (pintype "input"))
      (node (ref "Q1") (pin "D") (pinfunction "D_D") (pintype "passive"))
      (node (ref "TP_VIN_SW") (pin "TP") (pinfunction "TP_TP") (pintype "input"))
    )
    (net (code "5") (name "A0") (class "Default")
      (node (ref "IC3") (pin "3") (pinfunction "QD_3") (pintype "tri_state"))
      (node (ref "IC7") (pin "A0") (pinfunction "A0_A0") (pintype "passive"))
    )
    (net (code "6") (name "A1") (class "Default")
      (node (ref "IC3") (pin "2") (pinfunction "QC_2") (pintype "tri_state"))
      (node (ref "IC7") (pin "A1") (pinfunction "A1_A1") (pintype "passive"))
    )
    (net (code "7") (name "AUDIO_FML") (class "Default")
      (node (ref "C6") (pin "+") (pinfunction "+_+") (pintype "passive"))
      (node (ref "IC7") (pin "MOL") (pinfunction "MOL_MOL") (pintype "passive"))
      (node (ref "S1") (pin "6") (pinfunction "2_6") (pintype "passive"))
    )
    (net (code "8") (name "AUDIO_FMR") (class "Default")
      (node (ref "C7") (pin "+") (pinfunction "+_+") (pintype "passive"))
      (node (ref "IC7") (pin "MOR") (pinfunction "MOR_MOR") (pintype "passive"))
      (node (ref "S1") (pin "8") (pinfunction "2_8") (pintype "passive"))
    )
    (net (code "9") (name "AUDIO_LINEL") (class "Default")
      (node (ref "C16") (pin "+") (pinfunction "+_+") (pintype "passive"))
      (node (ref "R17") (pin "1") (pinfunction "1_1") (pintype "passive"))
    )
    (net (code "10") (name "AUDIO_LINER") (class "Default")
      (node (ref "C17") (pin "+") (pinfunction "+_+") (pintype "passive"))
      (node (ref "R18") (pin "1") (pinfunction "1_1") (pintype "passive"))
    )
    (net (code "11") (name "AUDIO_PSG") (class "Default")
      (node (ref "C8") (pin "-") (pinfunction "-_-") (pintype "passive"))
      (node (ref "IC8") (pin "SND_OUT") (pinfunction "SND_OUT_SND_OUT") (pintype "passive"))
      (node (ref "R10") (pin "1") (pinfunction "1_1") (pintype "passive"))
    )
    (net (code "12") (name "CLK_FM") (class "Default")
      (node (ref "IC12") (pin "29") (pinfunction "IO5_29") (pintype "bidirectional"))
      (node (ref "IC7") (pin "M") (pinfunction "M_M") (pintype "passive"))
    )
    (net (code "13") (name "CLK_PSG") (class "Default")
      (node (ref "IC12") (pin "9") (pinfunction "IO33_9") (pintype "bidirectional"))
      (node (ref "IC8") (pin "CLOCK") (pinfunction "CLOCK_CLOCK") (pintype "passive"))
    )
    (net (code "14") (name "D0") (class "Default")
      (node (ref "IC2") (pin "15") (pinfunction "QA_15") (pintype "tri_state"))
      (node (ref "IC7") (pin "D0") (pinfunction "D0_D0") (pintype "passive"))
      (node (ref "IC8") (pin "D7") (pinfunction "D7_D7") (pintype "passive"))
    )
    (net (code "15") (name "D1") (class "Default")
      (node (ref "IC2") (pin "1") (pinfunction "QB_1") (pintype "tri_state"))
      (node (ref "IC7") (pin "D1") (pinfunction "D1_D1") (pintype "passive"))
      (node (ref "IC8") (pin "D6") (pinfunction "D6_D6") (pintype "passive"))
    )
    (net (code "16") (name "D2") (class "Default")
      (node (ref "IC2") (pin "2") (pinfunction "QC_2") (pintype "tri_state"))
      (node (ref "IC7") (pin "D2") (pinfunction "D2_D2") (pintype "passive"))
      (node (ref "IC8") (pin "D5") (pinfunction "D5_D5") (pintype "passive"))
    )
    (net (code "17") (name "D3") (class "Default")
      (node (ref "IC2") (pin "3") (pinfunction "QD_3") (pintype "tri_state"))
      (node (ref "IC7") (pin "D3") (pinfunction "D3_D3") (pintype "passive"))
      (node (ref "IC8") (pin "D4") (pinfunction "D4_D4") (pintype "passive"))
    )
    (net (code "18") (name "D4") (class "Default")
      (node (ref "IC2") (pin "4") (pinfunction "QE_4") (pintype "tri_state"))
      (node (ref "IC7") (pin "D4") (pinfunction "D4_D4") (pintype "passive"))
      (node (ref "IC8") (pin "D3") (pinfunction "D3_D3") (pintype "passive"))
    )
    (net (code "19") (name "D5") (class "Default")
      (node (ref "IC2") (pin "5") (pinfunction "QF_5") (pintype "tri_state"))
      (node (ref "IC7") (pin "D5") (pinfunction "D5_D5") (pintype "passive"))
      (node (ref "IC8") (pin "D2") (pinfunction "D2_D2") (pintype "passive"))
    )
    (net (code "20") (name "D6") (class "Default")
      (node (ref "IC2") (pin "6") (pinfunction "QG_6") (pintype "tri_state"))
      (node (ref "IC7") (pin "D6") (pinfunction "D6_D6") (pintype "passive"))
      (node (ref "IC8") (pin "D1") (pinfunction "D1_D1") (pintype "passive"))
    )
    (net (code "21") (name "D7") (class "Default")
      (node (ref "IC2") (pin "7") (pinfunction "QH_7") (pintype "tri_state"))
      (node (ref "IC7") (pin "D7") (pinfunction "D7_D7") (pintype "passive"))
      (node (ref "IC8") (pin "D0") (pinfunction "D0_D0") (pintype "passive"))
    )
    (net (code "22") (name "ESP32_RESET") (class "Default")
      (node (ref "C9") (pin "1") (pinfunction "1_1") (pintype "passive"))
      (node (ref "D2") (pin "A") (pinfunction "A_A") (pintype "passive"))
      (node (ref "IC12") (pin "3") (pinfunction "EN_3") (pintype "bidirectional"))
      (node (ref "R13") (pin "2") (pinfunction "2_2") (pintype "passive"))
      (node (ref "TP_RESET") (pin "TP") (pinfunction "TP_TP") (pintype "input"))
    )
    (net (code "23") (name "FM1") (class "Default")
      (node (ref "IC9") (pin "14") (pinfunction "LED7_14") (pintype "bidirectional"))
      (node (ref "LED1") (pin "K") (pinfunction "C_K") (pintype "passive"))
    )
    (net (code "24") (name "FM1N") (class "Default")
      (node (ref "LED1") (pin "A") (pinfunction "A_A") (pintype "passive"))
      (node (ref "RN1") (pin "8") (pinfunction "8_8") (pintype "passive"))
    )
    (net (code "25") (name "FM2") (class "Default")
      (node (ref "IC9") (pin "7") (pinfunction "LED1_7") (pintype "bidirectional"))
      (node (ref "LED2") (pin "K") (pinfunction "C_K") (pintype "passive"))
    )
    (net (code "26") (name "FM2N") (class "Default")
      (node (ref "LED2") (pin "A") (pinfunction "A_A") (pintype "passive"))
      (node (ref "RN1") (pin "7") (pinfunction "7_7") (pintype "passive"))
    )
    (net (code "27") (name "FM3") (class "Default")
      (node (ref "IC9") (pin "8") (pinfunction "LED2_8") (pintype "bidirectional"))
      (node (ref "LED3") (pin "K") (pinfunction "C_K") (pintype "passive"))
    )
    (net (code "28") (name "FM3N") (class "Default")
      (node (ref "LED3") (pin "A") (pinfunction "A_A") (pintype "passive"))
      (node (ref "RN1") (pin "5") (pinfunction "5_5") (pintype "passive"))
    )
    (net (code "29") (name "FM4") (class "Default")
      (node (ref "IC9") (pin "9") (pinfunction "LED3_9") (pintype "bidirectional"))
      (node (ref "LED4") (pin "K") (pinfunction "C_K") (pintype "passive"))
    )
    (net (code "30") (name "FM4N") (class "Default")
      (node (ref "LED4") (pin "A") (pinfunction "A_A") (pintype "passive"))
      (node (ref "RN1") (pin "3") (pinfunction "3_3") (pintype "passive"))
    )
    (net (code "31") (name "FM5") (class "Default")
      (node (ref "IC10") (pin "7") (pinfunction "LED1_7") (pintype "bidirectional"))
      (node (ref "LED5") (pin "K") (pinfunction "C_K") (pintype "passive"))
    )
    (net (code "32") (name "FM5N") (class "Default")
      (node (ref "LED5") (pin "A") (pinfunction "A_A") (pintype "passive"))
      (node (ref "RN3") (pin "4") (pinfunction "4_4") (pintype "passive"))
    )
    (net (code "33") (name "FM6") (class "Default")
      (node (ref "IC10") (pin "8") (pinfunction "LED2_8") (pintype "bidirectional"))
      (node (ref "LED6") (pin "K") (pinfunction "C_K") (pintype "passive"))
    )
    (net (code "34") (name "FM6N") (class "Default")
      (node (ref "LED6") (pin "A") (pinfunction "A_A") (pintype "passive"))
      (node (ref "RN3") (pin "3") (pinfunction "3_3") (pintype "passive"))
    )
    (net (code "35") (name "FMS") (class "Default")
      (node (ref "IC10") (pin "9") (pinfunction "LED3_9") (pintype "bidirectional"))
      (node (ref "LED7") (pin "K") (pinfunction "C_K") (pintype "passive"))
    )
    (net (code "36") (name "FMSN") (class "Default")
      (node (ref "LED7") (pin "A") (pinfunction "A_A") (pintype "passive"))
      (node (ref "RN3") (pin "2") (pinfunction "2_2") (pintype "passive"))
    )
    (net (code "37") (name "GND") (class "Default")
      (node (ref "C1") (pin "2") (pinfunction "2_2") (pintype "passive"))
      (node (ref "C10") (pin "-") (pinfunction "-_-") (pintype "passive"))
      (node (ref "C11") (pin "2") (pinfunction "2_2") (pintype "passive"))
      (node (ref "C12") (pin "2") (pinfunction "2_2") (pintype "passive"))
      (node (ref "C13") (pin "-") (pinfunction "-_-") (pintype "passive"))
      (node (ref "C18") (pin "2") (pinfunction "2_2") (pintype "passive"))
      (node (ref "C19") (pin "2") (pinfunction "2_2") (pintype "passive"))
      (node (ref "C2") (pin "-") (pinfunction "-_-") (pintype "passive"))
      (node (ref "C22") (pin "2") (pinfunction "2_2") (pintype "passive"))
      (node (ref "C23") (pin "2") (pinfunction "2_2") (pintype "passive"))
      (node (ref "C24") (pin "2") (pinfunction "2_2") (pintype "passive"))
      (node (ref "C25") (pin "2") (pinfunction "2_2") (pintype "passive"))
      (node (ref "C26") (pin "-") (pinfunction "-_-") (pintype "passive"))
      (node (ref "C28") (pin "-") (pinfunction "-_-") (pintype "passive"))
      (node (ref "C29") (pin "2") (pinfunction "2_2") (pintype "passive"))
      (node (ref "C30") (pin "2") (pinfunction "2_2") (pintype "passive"))
      (node (ref "C31") (pin "2") (pinfunction "2_2") (pintype "passive"))
      (node (ref "C32") (pin "2") (pinfunction "2_2") (pintype "passive"))
      (node (ref "C33") (pin "-") (pinfunction "-_-") (pintype "passive"))
      (node (ref "C34") (pin "2") (pinfunction "2_2") (pintype "passive"))
      (node (ref "C35") (pin "2") (pinfunction "2_2") (pintype "passive"))
      (node (ref "C5") (pin "2") (pinfunction "2_2") (pintype "passive"))
      (node (ref "C9") (pin "2") (pinfunction "2_2") (pintype "passive"))
      (node (ref "IC1") (pin "2") (pinfunction "GND_2") (pintype "passive"))
      (node (ref "IC1") (pin "TAB") (pinfunction "GND_TAB") (pintype "passive"))
      (node (ref "IC10") (pin "10") (pinfunction "VSS_10") (pintype "power_in"))
      (node (ref "IC10") (pin "15") (pinfunction "~{OE}_15") (pintype "bidirectional"))
      (node (ref "IC10") (pin "16") (pinfunction "A5_16") (pintype "bidirectional"))
      (node (ref "IC10") (pin "17") (pinfunction "A6_17") (pintype "bidirectional"))
      (node (ref "IC10") (pin "2") (pinfunction "A1_2") (pintype "bidirectional"))
      (node (ref "IC10") (pin "3") (pinfunction "A2_3") (pintype "bidirectional"))
      (node (ref "IC10") (pin "4") (pinfunction "A3_4") (pintype "bidirectional"))
      (node (ref "IC10") (pin "5") (pinfunction "A4_5") (pintype "bidirectional"))
      (node (ref "IC11") (pin "4") (pinfunction "GND_4") (pintype "power_in"))
      (node (ref "IC11") (pin "5") (pinfunction "SHUTDOWN_5") (pintype "input"))
      (node (ref "IC12") (pin "1") (pinfunction "GND_1") (pintype "bidirectional"))
      (node (ref "IC12") (pin "15") (pinfunction "GND_15") (pintype "bidirectional"))
      (node (ref "IC12") (pin "38") (pinfunction "GND_38") (pintype "bidirectional"))
      (node (ref "IC12") (pin "GND") (pinfunction "GND_GND") (pintype "bidirectional"))
      (node (ref "IC14") (pin "1") (pinfunction "GND_1") (pintype "bidirectional"))
      (node (ref "IC2") (pin "13") (pinfunction "G_13") (pintype "input"))
      (node (ref "IC2") (pin "8") (pinfunction "GND_8") (pintype "power_in"))
      (node (ref "IC3") (pin "13") (pinfunction "G_13") (pintype "input"))
      (node (ref "IC3") (pin "8") (pinfunction "GND_8") (pintype "power_in"))
      (node (ref "IC4") (pin "10") (pinfunction "VSS_10") (pintype "power_in"))
      (node (ref "IC4") (pin "15") (pinfunction "A0_15") (pintype "input"))
      (node (ref "IC4") (pin "16") (pinfunction "A1_16") (pintype "input"))
      (node (ref "IC4") (pin "17") (pinfunction "A2_17") (pintype "input"))
      (node (ref "IC5") (pin "4") (pinfunction "V-_4") (pintype "power_in"))
      (node (ref "IC6") (pin "2") (pinfunction "GND_2") (pintype "passive"))
      (node (ref "IC7") (pin "AGND") (pinfunction "AGND_AGND") (pintype "passive"))
      (node (ref "IC7") (pin "GND@1") (pinfunction "GND_GND@1") (pintype "passive"))
      (node (ref "IC7") (pin "GND@2") (pinfunction "GND_GND@2") (pintype "passive"))
      (node (ref "IC8") (pin "GND") (pinfunction "GND_GND") (pintype "passive"))
      (node (ref "IC9") (pin "1") (pinfunction "A0_1") (pintype "bidirectional"))
      (node (ref "IC9") (pin "10") (pinfunction "VSS_10") (pintype "power_in"))
      (node (ref "IC9") (pin "15") (pinfunction "~{OE}_15") (pintype "bidirectional"))
      (node (ref "IC9") (pin "16") (pinfunction "A5_16") (pintype "bidirectional"))
      (node (ref "IC9") (pin "2") (pinfunction "A1_2") (pintype "bidirectional"))
      (node (ref "IC9") (pin "3") (pinfunction "A2_3") (pintype "bidirectional"))
      (node (ref "IC9") (pin "4") (pinfunction "A3_4") (pintype "bidirectional"))
      (node (ref "IC9") (pin "5") (pinfunction "A4_5") (pintype "bidirectional"))
      (node (ref "J1") (pin "GND") (pinfunction "GND_GND") (pintype "power_in"))
      (node (ref "J1") (pin "SHLD1") (pinfunction "SHIELD_SHLD1") (pintype "bidirectional"))
      (node (ref "J1") (pin "SHLD2") (pinfunction "SHIELD_SHLD2") (pintype "bidirectional"))
      (node (ref "J2") (pin "1") (pinfunction "SLEEVE_1") (pintype "passive"))
      (node (ref "J3") (pin "12") (pinfunction "COMMON_GROUND_1_12") (pintype "bidirectional"))
      (node (ref "J3") (pin "13") (pinfunction "COMMON_GROUND_2_13") (pintype "bidirectional"))
      (node (ref "J3") (pin "14") (pinfunction "COMMON_GROUND_3_14") (pintype "bidirectional"))
      (node (ref "J3") (pin "15") (pinfunction "COMMON_GROUND_4_15") (pintype "bidirectional"))
      (node (ref "J3") (pin "3") (pinfunction "3_3") (pintype "bidirectional"))
      (node (ref "J3") (pin "6") (pinfunction "6_6") (pintype "bidirectional"))
      (node (ref "J4") (pin "GND") (pinfunction "GND_GND") (pintype "bidirectional"))
      (node (ref "J4") (pin "GNDBREAK") (pinfunction "GNDBREAK_GNDBREAK") (pintype "bidirectional"))
      (node (ref "JP1") (pin "2") (pinfunction "2_2") (pintype "passive"))
      (node (ref "KK1") (pin "B") (pinfunction "K_B") (pintype "passive"))
      (node (ref "KK1") (pin "B1") (pinfunction "K_B1") (pintype "passive"))
      (node (ref "R10") (pin "2") (pinfunction "2_2") (pintype "passive"))
      (node (ref "R14") (pin "1-1") (pinfunction "A_1-1") (pintype "passive"))
      (node (ref "R14") (pin "2-1") (pinfunction "A_2-1") (pintype "passive"))
      (node (ref "R21") (pin "1") (pinfunction "1_1") (pintype "passive"))
      (node (ref "R22") (pin "1") (pinfunction "1_1") (pintype "passive"))
      (node (ref "R25") (pin "1") (pinfunction "1_1") (pintype "passive"))
      (node (ref "R27") (pin "1") (pinfunction "1_1") (pintype "passive"))
      (node (ref "R28") (pin "1") (pinfunction "1_1") (pintype "passive"))
      (node (ref "S2") (pin "2") (pinfunction "2_2") (pintype "passive"))
      (node (ref "SWA") (pin "3") (pinfunction "2_3") (pintype "passive"))
      (node (ref "SWB") (pin "3") (pinfunction "2_3") (pintype "passive"))
      (node (ref "SWC") (pin "3") (pinfunction "2_3") (pintype "passive"))
      (node (ref "SWDOWN") (pin "3") (pinfunction "2_3") (pintype "passive"))
      (node (ref "SWLEFT") (pin "3") (pinfunction "2_3") (pintype "passive"))
      (node (ref "SWRIGHT") (pin "3") (pinfunction "2_3") (pintype "passive"))
      (node (ref "SWUP") (pin "3") (pinfunction "2_3") (pintype "passive"))
      (node (ref "TP_GND") (pin "TP") (pinfunction "TP_TP") (pintype "input"))
    )
    (net (code "38") (name "KEY_A") (class "Default")
      (node (ref "IC4") (pin "23") (pinfunction "GPA2_23") (pintype "bidirectional"))
      (node (ref "SWA") (pin "1") (pinfunction "1_1") (pintype "passive"))
    )
    (net (code "39") (name "KEY_B") (class "Default")
      (node (ref "IC4") (pin "22") (pinfunction "GPA1_22") (pintype "bidirectional"))
      (node (ref "SWB") (pin "1") (pinfunction "1_1") (pintype "passive"))
    )
    (net (code "40") (name "KEY_C") (class "Default")
      (node (ref "IC4") (pin "21") (pinfunction "GPA0_21") (pintype "bidirectional"))
      (node (ref "SWC") (pin "1") (pinfunction "1_1") (pintype "passive"))
    )
    (net (code "41") (name "KEY_DOWN") (class "Default")
      (node (ref "IC4") (pin "25") (pinfunction "GPA4_25") (pintype "bidirectional"))
      (node (ref "SWDOWN") (pin "1") (pinfunction "1_1") (pintype "passive"))
    )
    (net (code "42") (name "KEY_INT") (class "Default")
      (node (ref "IC12") (pin "7") (pinfunction "IO35_7") (pintype "bidirectional"))
      (node (ref "IC4") (pin "20") (pinfunction "INTA_20") (pintype "output"))
    )
    (net (code "43") (name "KEY_LEFT") (class "Default")
      (node (ref "IC4") (pin "26") (pinfunction "GPA5_26") (pintype "bidirectional"))
      (node (ref "SWLEFT") (pin "1") (pinfunction "1_1") (pintype "passive"))
    )
    (net (code "44") (name "KEY_RIGHT") (class "Default")
      (node (ref "IC4") (pin "24") (pinfunction "GPA3_24") (pintype "bidirectional"))
      (node (ref "SWRIGHT") (pin "1") (pinfunction "1_1") (pintype "passive"))
    )
    (net (code "45") (name "KEY_UP") (class "Default")
      (node (ref "IC4") (pin "27") (pinfunction "GPA6_27") (pintype "bidirectional"))
      (node (ref "SWUP") (pin "1") (pinfunction "1_1") (pintype "passive"))
    )
    (net (code "46") (name "LCD_CLK") (class "Default")
      (node (ref "IC12") (pin "8") (pinfunction "IO32_8") (pintype "bidirectional"))
      (node (ref "JP1") (pin "7") (pinfunction "7_7") (pintype "passive"))
    )
    (net (code "47") (name "LCD_DC") (class "Default")
      (node (ref "IC12") (pin "36") (pinfunction "IO22_36") (pintype "bidirectional"))
      (node (ref "JP1") (pin "5") (pinfunction "5_5") (pintype "passive"))
    )
    (net (code "48") (name "LCD_MOSI") (class "Default")
      (node (ref "IC12") (pin "12") (pinfunction "IO27_12") (pintype "bidirectional"))
      (node (ref "JP1") (pin "6") (pinfunction "6_6") (pintype "passive"))
    )
    (net (code "49") (name "LCD_{slash}CS") (class "Default")
      (node (ref "IC12") (pin "33") (pinfunction "IO21_33") (pintype "bidirectional"))
      (node (ref "JP1") (pin "3") (pinfunction "3_3") (pintype "passive"))
    )
    (net (code "50") (name "Net-(C8-Pad+)") (class "Default")
      (node (ref "C8") (pin "+") (pinfunction "+_+") (pintype "passive"))
      (node (ref "R23") (pin "E") (pinfunction "E_E") (pintype "passive"))
    )
    (net (code "51") (name "Net-(C20-Pad-)") (class "Default")
      (node (ref "C20") (pin "-") (pinfunction "-_-") (pintype "passive"))
      (node (ref "R19") (pin "1") (pinfunction "1_1") (pintype "passive"))
    )
    (net (code "52") (name "Net-(C21-Pad-)") (class "Default")
      (node (ref "C21") (pin "-") (pinfunction "-_-") (pintype "passive"))
      (node (ref "R20") (pin "1") (pinfunction "1_1") (pintype "passive"))
    )
    (net (code "53") (name "Net-(D3-PadA)") (class "Default")
      (node (ref "D3") (pin "A") (pinfunction "A_A") (pintype "passive"))
      (node (ref "J4") (pin "PWR") (pinfunction "PWR_PWR") (pintype "bidirectional"))
    )
    (net (code "54") (name "Net-(D3-PadC)") (class "Default")
      (node (ref "D3") (pin "C") (pinfunction "C_C") (pintype "passive"))
      (node (ref "Q1") (pin "S") (pinfunction "S_S") (pintype "passive"))
      (node (ref "R26") (pin "2") (pinfunction "2_2") (pintype "passive"))
      (node (ref "TP_VIN") (pin "TP") (pinfunction "TP_TP") (pintype "input"))
    )
    (net (code "55") (name "Net-(IC2A-SER)") (class "Default")
      (node (ref "IC2") (pin "14") (pinfunction "SER_14") (pintype "input"))
      (node (ref "IC3") (pin "9") (pinfunction "QH*_9") (pintype "tri_state"))
    )
    (net (code "56") (name "Net-(IC5A--IN)") (class "Default")
      (node (ref "C3") (pin "1") (pinfunction "1_1") (pintype "passive"))
      (node (ref "IC5") (pin "2") (pinfunction "-IN_2") (pintype "input"))
      (node (ref "R3") (pin "2") (pinfunction "2_2") (pintype "passive"))
      (node (ref "R6") (pin "1") (pinfunction "1_1") (pintype "passive"))
      (node (ref "R9") (pin "1") (pinfunction "1_1") (pintype "passive"))
    )
    (net (code "57") (name "Net-(IC5A-OUT)") (class "Default")
      (node (ref "C14") (pin "+") (pinfunction "+_+") (pintype "passive"))
      (node (ref "C3") (pin "2") (pinfunction "2_2") (pintype "passive"))
      (node (ref "IC5") (pin "1") (pinfunction "OUT_1") (pintype "output"))
      (node (ref "R3") (pin "1") (pinfunction "1_1") (pintype "passive"))
    )
    (net (code "58") (name "Net-(IC5B--IN)") (class "Default")
      (node (ref "C4") (pin "1") (pinfunction "1_1") (pintype "passive"))
      (node (ref "IC5") (pin "6") (pinfunction "-IN_6") (pintype "input"))
      (node (ref "R11") (pin "1") (pinfunction "1_1") (pintype "passive"))
      (node (ref "R4") (pin "2") (pinfunction "2_2") (pintype "passive"))
      (node (ref "R8") (pin "1") (pinfunction "1_1") (pintype "passive"))
    )
    (net (code "59") (name "Net-(IC5B-OUT)") (class "Default")
      (node (ref "C15") (pin "+") (pinfunction "+_+") (pintype "passive"))
      (node (ref "C4") (pin "2") (pinfunction "2_2") (pintype "passive"))
      (node (ref "IC5") (pin "7") (pinfunction "OUT_7") (pintype "output"))
      (node (ref "R4") (pin "1") (pinfunction "1_1") (pintype "passive"))
    )
    (net (code "60") (name "Net-(IC11-BYPASS)") (class "Default")
      (node (ref "C19") (pin "1") (pinfunction "1_1") (pintype "passive"))
      (node (ref "IC11") (pin "3") (pinfunction "BYPASS_3") (pintype "input"))
    )
    (net (code "61") (name "Net-(IC11-IN1-)") (class "Default")
      (node (ref "IC11") (pin "2") (pinfunction "IN1-_2") (pintype "input"))
      (node (ref "R16") (pin "1") (pinfunction "1_1") (pintype "passive"))
      (node (ref "R17") (pin "2") (pinfunction "2_2") (pintype "passive"))
    )
    (net (code "62") (name "Net-(IC11-IN2-)") (class "Default")
      (node (ref "IC11") (pin "6") (pinfunction "IN2-_6") (pintype "input"))
      (node (ref "R15") (pin "1") (pinfunction "1_1") (pintype "passive"))
      (node (ref "R18") (pin "2") (pinfunction "2_2") (pintype "passive"))
    )
    (net (code "63") (name "Net-(IC11-VO1)") (class "Default")
      (node (ref "C20") (pin "+") (pinfunction "+_+") (pintype "passive"))
      (node (ref "IC11") (pin "1") (pinfunction "VO1_1") (pintype "output"))
      (node (ref "R16") (pin "2") (pinfunction "2_2") (pintype "passive"))
    )
    (net (code "64") (name "Net-(IC11-VO2)") (class "Default")
      (node (ref "C21") (pin "+") (pinfunction "+_+") (pintype "passive"))
      (node (ref "IC11") (pin "7") (pinfunction "VO2_7") (pintype "output"))
      (node (ref "R15") (pin "2") (pinfunction "2_2") (pintype "passive"))
    )
    (net (code "65") (name "Net-(IC12-IO25)") (class "Default")
      (node (ref "EX_A") (pin "TP") (pinfunction "TP_TP") (pintype "input"))
      (node (ref "IC12") (pin "10") (pinfunction "IO25_10") (pintype "bidirectional"))
    )
    (net (code "66") (name "Net-(IC12-IO26)") (class "Default")
      (node (ref "EX_B") (pin "TP") (pinfunction "TP_TP") (pintype "input"))
      (node (ref "IC12") (pin "11") (pinfunction "IO26_11") (pintype "bidirectional"))
    )
    (net (code "67") (name "Net-(IC14-DTR)") (class "Default")
      (node (ref "D1") (pin "C") (pinfunction "C_C") (pintype "passive"))
      (node (ref "IC14") (pin "13") (pinfunction "DTR_13") (pintype "bidirectional"))
    )
    (net (code "68") (name "Net-(IC14-RTS)") (class "Default")
      (node (ref "D2") (pin "C") (pinfunction "C_C") (pintype "passive"))
      (node (ref "IC14") (pin "14") (pinfunction "RTS_14") (pintype "bidirectional"))
    )
    (net (code "69") (name "Net-(IC14-XI)") (class "Default")
      (node (ref "C22") (pin "1") (pinfunction "1_1") (pintype "passive"))
      (node (ref "IC14") (pin "7") (pinfunction "XI_7") (pintype "bidirectional"))
      (node (ref "Y1") (pin "1") (pinfunction "1_1") (pintype "passive"))
    )
    (net (code "70") (name "Net-(IC14-XO)") (class "Default")
      (node (ref "C23") (pin "1") (pinfunction "1_1") (pintype "passive"))
      (node (ref "IC14") (pin "8") (pinfunction "XO_8") (pintype "bidirectional"))
      (node (ref "Y1") (pin "2") (pinfunction "2_2") (pintype "passive"))
    )
    (net (code "71") (name "Net-(J2-RING)") (class "Default")
      (node (ref "J2") (pin "3") (pinfunction "RING_3") (pintype "passive"))
      (node (ref "R20") (pin "2") (pinfunction "2_2") (pintype "passive"))
      (node (ref "R28") (pin "2") (pinfunction "2_2") (pintype "passive"))
    )
    (net (code "72") (name "Net-(J2-TIP)") (class "Default")
      (node (ref "J2") (pin "2") (pinfunction "TIP_2") (pintype "passive"))
      (node (ref "R19") (pin "2") (pinfunction "2_2") (pintype "passive"))
      (node (ref "R27") (pin "2") (pinfunction "2_2") (pintype "passive"))
    )
    (net (code "73") (name "Net-(JP1-Pad8)") (class "Default")
      (node (ref "JP1") (pin "8") (pinfunction "8_8") (pintype "passive"))
      (node (ref "R12") (pin "1") (pinfunction "1_1") (pintype "passive"))
    )
    (net (code "74") (name "Net-(Q1-PadG)") (class "Default")
      (node (ref "Q1") (pin "G") (pinfunction "G_G") (pintype "passive"))
      (node (ref "R26") (pin "1") (pinfunction "1_1") (pintype "passive"))
      (node (ref "S2") (pin "3") (pinfunction "3_3") (pintype "passive"))
    )
    (net (code "75") (name "Net-(R14A-E)") (class "Default")
      (node (ref "C14") (pin "-") (pinfunction "-_-") (pintype "passive"))
      (node (ref "R14") (pin "1-3") (pinfunction "E_1-3") (pintype "passive"))
    )
    (net (code "76") (name "Net-(R14A-S)") (class "Default")
      (node (ref "C16") (pin "-") (pinfunction "-_-") (pintype "passive"))
      (node (ref "R14") (pin "1-2") (pinfunction "S_1-2") (pintype "passive"))
    )
    (net (code "77") (name "Net-(R14B-E)") (class "Default")
      (node (ref "C15") (pin "-") (pinfunction "-_-") (pintype "passive"))
      (node (ref "R14") (pin "2-3") (pinfunction "E_2-3") (pintype "passive"))
    )
    (net (code "78") (name "Net-(R14B-S)") (class "Default")
      (node (ref "C17") (pin "-") (pinfunction "-_-") (pintype "passive"))
      (node (ref "R14") (pin "2-2") (pinfunction "S_2-2") (pintype "passive"))
    )
    (net (code "79") (name "Net-(R22-Pad2)") (class "Default")
      (node (ref "R22") (pin "2") (pinfunction "2_2") (pintype "passive"))
      (node (ref "S1") (pin "1") (pinfunction "1_1") (pintype "passive"))
    )
    (net (code "80") (name "Net-(R23-PadS)") (class "Default")
      (node (ref "R23") (pin "S") (pinfunction "S_S") (pintype "passive"))
      (node (ref "R6") (pin "2") (pinfunction "2_2") (pintype "passive"))
      (node (ref "R8") (pin "2") (pinfunction "2_2") (pintype "passive"))
    )
    (net (code "81") (name "Net-(S1B-1)") (class "Default")
      (node (ref "R11") (pin "2") (pinfunction "2_2") (pintype "passive"))
      (node (ref "R7") (pin "1") (pinfunction "1_1") (pintype "passive"))
      (node (ref "S1") (pin "2") (pinfunction "1_2") (pintype "passive"))
    )
    (net (code "82") (name "Net-(S1B-2)") (class "Default")
      (node (ref "C7") (pin "-") (pinfunction "-_-") (pintype "passive"))
      (node (ref "R7") (pin "2") (pinfunction "2_2") (pintype "passive"))
      (node (ref "S1") (pin "7") (pinfunction "2_7") (pintype "passive"))
    )
    (net (code "83") (name "Net-(S1C-1)") (class "Default")
      (node (ref "R21") (pin "2") (pinfunction "2_2") (pintype "passive"))
      (node (ref "S1") (pin "3") (pinfunction "1_3") (pintype "passive"))
    )
    (net (code "84") (name "Net-(S1D-1)") (class "Default")
      (node (ref "R5") (pin "1") (pinfunction "1_1") (pintype "passive"))
      (node (ref "R9") (pin "2") (pinfunction "2_2") (pintype "passive"))
      (node (ref "S1") (pin "4") (pinfunction "1_4") (pintype "passive"))
    )
    (net (code "85") (name "Net-(S1D-2)") (class "Default")
      (node (ref "C6") (pin "-") (pinfunction "-_-") (pintype "passive"))
      (node (ref "R5") (pin "2") (pinfunction "2_2") (pintype "passive"))
      (node (ref "S1") (pin "5") (pinfunction "2_5") (pintype "passive"))
    )
    (net (code "86") (name "PSG1") (class "Default")
      (node (ref "IC9") (pin "6") (pinfunction "LED0_6") (pintype "bidirectional"))
      (node (ref "LED8") (pin "K") (pinfunction "C_K") (pintype "passive"))
    )
    (net (code "87") (name "PSG1N") (class "Default")
      (node (ref "LED8") (pin "A") (pinfunction "A_A") (pintype "passive"))
      (node (ref "RN1") (pin "9") (pinfunction "9_9") (pintype "passive"))
    )
    (net (code "88") (name "PSG2") (class "Default")
      (node (ref "IC9") (pin "13") (pinfunction "LED6_13") (pintype "bidirectional"))
      (node (ref "LED9") (pin "K") (pinfunction "C_K") (pintype "passive"))
    )
    (net (code "89") (name "PSG2N") (class "Default")
      (node (ref "LED9") (pin "A") (pinfunction "A_A") (pintype "passive"))
      (node (ref "RN1") (pin "6") (pinfunction "6_6") (pintype "passive"))
    )
    (net (code "90") (name "PSG3") (class "Default")
      (node (ref "IC9") (pin "12") (pinfunction "LED5_12") (pintype "bidirectional"))
      (node (ref "LED10") (pin "K") (pinfunction "C_K") (pintype "passive"))
    )
    (net (code "91") (name "PSG3N") (class "Default")
      (node (ref "LED10") (pin "A") (pinfunction "A_A") (pintype "passive"))
      (node (ref "RN1") (pin "4") (pinfunction "4_4") (pintype "passive"))
    )
    (net (code "92") (name "PSGS") (class "Default")
      (node (ref "IC9") (pin "11") (pinfunction "LED4_11") (pintype "bidirectional"))
      (node (ref "LED11") (pin "K") (pinfunction "C_K") (pintype "passive"))
    )
    (net (code "93") (name "PSGSN") (class "Default")
      (node (ref "LED11") (pin "A") (pinfunction "A_A") (pintype "passive"))
      (node (ref "RN1") (pin "2") (pinfunction "2_2") (pintype "passive"))
    )
    (net (code "94") (name "RXD") (class "Default")
      (node (ref "IC12") (pin "34") (pinfunction "RXD0_34") (pintype "bidirectional"))
      (node (ref "IC14") (pin "2") (pinfunction "TX_2") (pintype "bidirectional"))
      (node (ref "TP_RX") (pin "TP") (pinfunction "TP_TP") (pintype "input"))
    )
    (net (code "95") (name "SCL") (class "Default")
      (node (ref "IC10") (pin "18") (pinfunction "SCL_18") (pintype "bidirectional"))
      (node (ref "IC12") (pin "27") (pinfunction "IO16_27") (pintype "bidirectional"))
      (node (ref "IC4") (pin "12") (pinfunction "SCL_12") (pintype "input"))
      (node (ref "IC9") (pin "18") (pinfunction "SCL_18") (pintype "bidirectional"))
      (node (ref "R2") (pin "1") (pinfunction "1_1") (pintype "passive"))
      (node (ref "TP_SCL") (pin "TP") (pinfunction "TP_TP") (pintype "input"))
    )
    (net (code "96") (name "SDA") (class "Default")
      (node (ref "IC10") (pin "19") (pinfunction "SDA_19") (pintype "bidirectional"))
      (node (ref "IC12") (pin "28") (pinfunction "IO17_28") (pintype "bidirectional"))
      (node (ref "IC4") (pin "13") (pinfunction "SDA_13") (pintype "bidirectional"))
      (node (ref "IC9") (pin "19") (pinfunction "SDA_19") (pintype "bidirectional"))
      (node (ref "R1") (pin "1") (pinfunction "1_1") (pintype "passive"))
      (node (ref "TP_SDA") (pin "TP") (pinfunction "TP_TP") (pintype "input"))
    )
    (net (code "97") (name "SD_CLK") (class "Default")
      (node (ref "IC12") (pin "13") (pinfunction "IO14_13") (pintype "bidirectional"))
      (node (ref "J3") (pin "5") (pinfunction "5_5") (pintype "bidirectional"))
      (node (ref "RN2") (pin "6") (pinfunction "6_6") (pintype "passive"))
    )
    (net (code "98") (name "SD_CMD") (class "Default")
      (node (ref "IC12") (pin "23") (pinfunction "IO15_23") (pintype "bidirectional"))
      (node (ref "J3") (pin "2") (pinfunction "2_2") (pintype "bidirectional"))
      (node (ref "RN2") (pin "7") (pinfunction "7_7") (pintype "passive"))
    )
    (net (code "99") (name "SD_D0") (class "Default")
      (node (ref "D1") (pin "A") (pinfunction "A_A") (pintype "passive"))
      (node (ref "IC12") (pin "24") (pinfunction "IO2_24") (pintype "bidirectional"))
      (node (ref "IC12") (pin "25") (pinfunction "IO0_25") (pintype "bidirectional"))
      (node (ref "J3") (pin "7") (pinfunction "7_7") (pintype "bidirectional"))
      (node (ref "RN2") (pin "3") (pinfunction "3_3") (pintype "passive"))
      (node (ref "TP_BOOTMODE") (pin "TP") (pinfunction "TP_TP") (pintype "input"))
    )
    (net (code "100") (name "SD_D1") (class "Default")
      (node (ref "IC12") (pin "26") (pinfunction "IO4_26") (pintype "bidirectional"))
      (node (ref "J3") (pin "8") (pinfunction "8_8") (pintype "bidirectional"))
      (node (ref "RN2") (pin "2") (pinfunction "2_2") (pintype "passive"))
    )
    (net (code "101") (name "SD_D2") (class "Default")
      (node (ref "IC12") (pin "14") (pinfunction "IO12_14") (pintype "bidirectional"))
      (node (ref "J3") (pin "9") (pinfunction "9_9") (pintype "bidirectional"))
      (node (ref "RN2") (pin "9") (pinfunction "9_9") (pintype "passive"))
    )
    (net (code "102") (name "SD_D3") (class "Default")
      (node (ref "IC12") (pin "16") (pinfunction "IO13_16") (pintype "bidirectional"))
      (node (ref "J3") (pin "1") (pinfunction "1_1") (pintype "bidirectional"))
      (node (ref "RN2") (pin "8") (pinfunction "8_8") (pintype "passive"))
    )
    (net (code "103") (name "SHCLK") (class "Default")
      (node (ref "IC12") (pin "31") (pinfunction "IO19_31") (pintype "bidirectional"))
      (node (ref "IC2") (pin "11") (pinfunction "SCK_11") (pintype "input"))
      (node (ref "IC3") (pin "11") (pinfunction "SCK_11") (pintype "input"))
    )
    (net (code "104") (name "SHDATA") (class "Default")
      (node (ref "IC12") (pin "37") (pinfunction "IO23_37") (pintype "bidirectional"))
      (node (ref "IC3") (pin "14") (pinfunction "SER_14") (pintype "input"))
    )
    (net (code "105") (name "SHSTO") (class "Default")
      (node (ref "IC12") (pin "30") (pinfunction "IO18_30") (pintype "bidirectional"))
      (node (ref "IC2") (pin "12") (pinfunction "RCK_12") (pintype "input"))
      (node (ref "IC3") (pin "12") (pinfunction "RCK_12") (pintype "input"))
    )
    (net (code "106") (name "TXD") (class "Default")
      (node (ref "IC12") (pin "35") (pinfunction "TXD0_35") (pintype "bidirectional"))
      (node (ref "IC14") (pin "3") (pinfunction "RX_3") (pintype "bidirectional"))
      (node (ref "TP_TX") (pin "TP") (pinfunction "TP_TP") (pintype "input"))
    )
    (net (code "107") (name "USB_N") (class "Default")
      (node (ref "IC14") (pin "6") (pinfunction "D-_6") (pintype "bidirectional"))
      (node (ref "J1") (pin "D-") (pinfunction "D-_D-") (pintype "bidirectional"))
    )
    (net (code "108") (name "USB_P") (class "Default")
      (node (ref "IC14") (pin "5") (pinfunction "D+_5") (pintype "bidirectional"))
      (node (ref "J1") (pin "D+") (pinfunction "D+_D+") (pintype "bidirectional"))
    )
    (net (code "109") (name "USERA") (class "Default")
      (node (ref "IC10") (pin "12") (pinfunction "LED5_12") (pintype "bidirectional"))
      (node (ref "LED12") (pin "K") (pinfunction "C_K") (pintype "passive"))
    )
    (net (code "110") (name "USERAN") (class "Default")
      (node (ref "LED12") (pin "A") (pinfunction "A_A") (pintype "passive"))
      (node (ref "RN3") (pin "8") (pinfunction "8_8") (pintype "passive"))
    )
    (net (code "111") (name "USERB") (class "Default")
      (node (ref "IC10") (pin "13") (pinfunction "LED6_13") (pintype "bidirectional"))
      (node (ref "LED13") (pin "K") (pinfunction "C_K") (pintype "passive"))
    )
    (net (code "112") (name "USERBN") (class "Default")
      (node (ref "LED13") (pin "A") (pinfunction "A_A") (pintype "passive"))
      (node (ref "RN3") (pin "9") (pinfunction "9_9") (pintype "passive"))
    )
    (net (code "113") (name "USERC") (class "Default")
      (node (ref "IC10") (pin "14") (pinfunction "LED7_14") (pintype "bidirectional"))
      (node (ref "LED14") (pin "K") (pinfunction "C_K") (pintype "passive"))
    )
    (net (code "114") (name "USERCN") (class "Default")
      (node (ref "LED14") (pin "A") (pinfunction "A_A") (pintype "passive"))
      (node (ref "RN3") (pin "7") (pinfunction "7_7") (pintype "passive"))
    )
    (net (code "115") (name "VBIAS") (class "Default")
      (node (ref "C2") (pin "+") (pinfunction "+_+") (pintype "passive"))
      (node (ref "IC5") (pin "3") (pinfunction "+IN_3") (pintype "input"))
      (node (ref "IC5") (pin "5") (pinfunction "+IN_5") (pintype "input"))
      (node (ref "R24") (pin "1") (pinfunction "1_1") (pintype "passive"))
      (node (ref "R25") (pin "2") (pinfunction "2_2") (pintype "passive"))
    )
    (net (code "116") (name "VBUS") (class "Default")
      (node (ref "J1") (pin "VBUS") (pinfunction "VBUS_VBUS") (pintype "power_in"))
    )
    (net (code "117") (name "unconnected-(IC2A-QH*-Pad9)") (class "Default")
      (node (ref "IC2") (pin "9") (pinfunction "QH*_9") (pintype "tri_state"))
    )
    (net (code "118") (name "unconnected-(IC3A-QA-Pad15)") (class "Default")
      (node (ref "IC3") (pin "15") (pinfunction "QA_15") (pintype "tri_state"))
    )
    (net (code "119") (name "unconnected-(IC3A-QB-Pad1)") (class "Default")
      (node (ref "IC3") (pin "1") (pinfunction "QB_1") (pintype "tri_state"))
    )
    (net (code "120") (name "unconnected-(IC4-GPA7-Pad28)") (class "Default")
      (node (ref "IC4") (pin "28") (pinfunction "GPA7_28") (pintype "bidirectional"))
    )
    (net (code "121") (name "unconnected-(IC4-GPB0-Pad1)") (class "Default")
      (node (ref "IC4") (pin "1") (pinfunction "GPB0_1") (pintype "bidirectional"))
    )
    (net (code "122") (name "unconnected-(IC4-GPB1-Pad2)") (class "Default")
      (node (ref "IC4") (pin "2") (pinfunction "GPB1_2") (pintype "bidirectional"))
    )
    (net (code "123") (name "unconnected-(IC4-GPB2-Pad3)") (class "Default")
      (node (ref "IC4") (pin "3") (pinfunction "GPB2_3") (pintype "bidirectional"))
    )
    (net (code "124") (name "unconnected-(IC4-GPB3-Pad4)") (class "Default")
      (node (ref "IC4") (pin "4") (pinfunction "GPB3_4") (pintype "bidirectional"))
    )
    (net (code "125") (name "unconnected-(IC4-GPB4-Pad5)") (class "Default")
      (node (ref "IC4") (pin "5") (pinfunction "GPB4_5") (pintype "bidirectional"))
    )
    (net (code "126") (name "unconnected-(IC4-GPB5-Pad6)") (class "Default")
      (node (ref "IC4") (pin "6") (pinfunction "GPB5_6") (pintype "bidirectional"))
    )
    (net (code "127") (name "unconnected-(IC4-GPB6-Pad7)") (class "Default")
      (node (ref "IC4") (pin "7") (pinfunction "GPB6_7") (pintype "bidirectional"))
    )
    (net (code "128") (name "unconnected-(IC4-GPB7-Pad8)") (class "Default")
      (node (ref "IC4") (pin "8") (pinfunction "GPB7_8") (pintype "bidirectional"))
    )
    (net (code "129") (name "unconnected-(IC4-INTB-Pad19)") (class "Default")
      (node (ref "IC4") (pin "19") (pinfunction "INTB_19") (pintype "output"))
    )
    (net (code "130") (name "unconnected-(IC7-PadNC)") (class "Default")
      (node (ref "IC7") (pin "NC") (pinfunction "NC_NC") (pintype "passive"))
    )
    (net (code "131") (name "unconnected-(IC7-Pad{slash}IRQ)") (class "Default")
      (node (ref "IC7") (pin "/IRQ") (pinfunction "/IRQ_/IRQ") (pintype "passive"))
    )
    (net (code "132") (name "unconnected-(IC8-PadNC)") (class "Default")
      (node (ref "IC8") (pin "NC") (pinfunction "NC_NC") (pintype "passive"))
    )
    (net (code "133") (name "unconnected-(IC8-PadREADY)") (class "Default")
      (node (ref "IC8") (pin "READY") (pinfunction "READY_READY") (pintype "passive"))
    )
    (net (code "134") (name "unconnected-(IC10-LED0-Pad6)") (class "Default")
      (node (ref "IC10") (pin "6") (pinfunction "LED0_6") (pintype "bidirectional"))
    )
    (net (code "135") (name "unconnected-(IC10-LED4-Pad11)") (class "Default")
      (node (ref "IC10") (pin "11") (pinfunction "LED4_11") (pintype "bidirectional"))
    )
    (net (code "136") (name "unconnected-(IC12-CLK-Pad20)") (class "Default")
      (node (ref "IC12") (pin "20") (pinfunction "CLK_20") (pintype "bidirectional"))
    )
    (net (code "137") (name "unconnected-(IC12-CMD-Pad19)") (class "Default")
      (node (ref "IC12") (pin "19") (pinfunction "CMD_19") (pintype "bidirectional"))
    )
    (net (code "138") (name "unconnected-(IC12-IO34-Pad6)") (class "Default")
      (node (ref "IC12") (pin "6") (pinfunction "IO34_6") (pintype "bidirectional"))
    )
    (net (code "139") (name "unconnected-(IC12-NC-Pad32)") (class "Default")
      (node (ref "IC12") (pin "32") (pinfunction "NC_32") (pintype "bidirectional"))
    )
    (net (code "140") (name "unconnected-(IC12-SD1-Pad22)") (class "Default")
      (node (ref "IC12") (pin "22") (pinfunction "SD1_22") (pintype "bidirectional"))
    )
    (net (code "141") (name "unconnected-(IC12-SD2-Pad17)") (class "Default")
      (node (ref "IC12") (pin "17") (pinfunction "SD2_17") (pintype "bidirectional"))
    )
    (net (code "142") (name "unconnected-(IC12-SD3-Pad18)") (class "Default")
      (node (ref "IC12") (pin "18") (pinfunction "SD3_18") (pintype "bidirectional"))
    )
    (net (code "143") (name "unconnected-(IC12-SDO-Pad21)") (class "Default")
      (node (ref "IC12") (pin "21") (pinfunction "SDO_21") (pintype "bidirectional"))
    )
    (net (code "144") (name "unconnected-(IC12-SENSOR_VN-Pad5)") (class "Default")
      (node (ref "IC12") (pin "5") (pinfunction "SENSOR_VN_5") (pintype "bidirectional"))
    )
    (net (code "145") (name "unconnected-(IC12-SENSOR_VP-Pad4)") (class "Default")
      (node (ref "IC12") (pin "4") (pinfunction "SENSOR_VP_4") (pintype "bidirectional"))
    )
    (net (code "146") (name "unconnected-(IC14-CTS-Pad9)") (class "Default")
      (node (ref "IC14") (pin "9") (pinfunction "CTS_9") (pintype "bidirectional"))
    )
    (net (code "147") (name "unconnected-(IC14-DCD-Pad12)") (class "Default")
      (node (ref "IC14") (pin "12") (pinfunction "DCD_12") (pintype "bidirectional"))
    )
    (net (code "148") (name "unconnected-(IC14-DSR-Pad10)") (class "Default")
      (node (ref "IC14") (pin "10") (pinfunction "DSR_10") (pintype "bidirectional"))
    )
    (net (code "149") (name "unconnected-(IC14-RI-Pad11)") (class "Default")
      (node (ref "IC14") (pin "11") (pinfunction "RI_11") (pintype "bidirectional"))
    )
    (net (code "150") (name "unconnected-(IC14-RS232-Pad15)") (class "Default")
      (node (ref "IC14") (pin "15") (pinfunction "RS232_15") (pintype "bidirectional"))
    )
    (net (code "151") (name "unconnected-(J2-RSH-Pad11)") (class "Default")
      (node (ref "J2") (pin "11") (pinfunction "RSH_11") (pintype "passive"))
    )
    (net (code "152") (name "unconnected-(J2-TSH-Pad10)") (class "Default")
      (node (ref "J2") (pin "10") (pinfunction "TSH_10") (pintype "passive"))
    )
    (net (code "153") (name "unconnected-(J3-CARD_DETECT-Pad10)") (class "Default")
      (node (ref "J3") (pin "10") (pinfunction "CARD_DETECT_10") (pintype "bidirectional"))
    )
    (net (code "154") (name "unconnected-(J3-WRITE_PROTECTION-Pad11)") (class "Default")
      (node (ref "J3") (pin "11") (pinfunction "WRITE_PROTECTION_11") (pintype "bidirectional"))
    )
    (net (code "155") (name "unconnected-(JP1-Pad9)") (class "Default")
      (node (ref "JP1") (pin "9") (pinfunction "9_9") (pintype "passive"))
    )
    (net (code "156") (name "unconnected-(JP1-Pad10)") (class "Default")
      (node (ref "JP1") (pin "10") (pinfunction "10_10") (pintype "passive"))
    )
    (net (code "157") (name "unconnected-(JP1-Pad11)") (class "Default")
      (node (ref "JP1") (pin "11") (pinfunction "11_11") (pintype "passive"))
    )
    (net (code "158") (name "unconnected-(JP1-Pad12)") (class "Default")
      (node (ref "JP1") (pin "12") (pinfunction "12_12") (pintype "passive"))
    )
    (net (code "159") (name "unconnected-(JP1-Pad13)") (class "Default")
      (node (ref "JP1") (pin "13") (pinfunction "13_13") (pintype "passive"))
    )
    (net (code "160") (name "unconnected-(JP1-Pad14)") (class "Default")
      (node (ref "JP1") (pin "14") (pinfunction "14_14") (pintype "passive"))
    )
    (net (code "161") (name "unconnected-(R23-PadA)") (class "Default")
      (node (ref "R23") (pin "A") (pinfunction "A_A") (pintype "passive"))
    )
    (net (code "162") (name "unconnected-(RN2-Pad4)") (class "Default")
      (node (ref "RN2") (pin "4") (pinfunction "4_4") (pintype "passive"))
    )
    (net (code "163") (name "unconnected-(RN2-Pad5)") (class "Default")
      (node (ref "RN2") (pin "5") (pinfunction "5_5") (pintype "passive"))
    )
    (net (code "164") (name "unconnected-(RN3-Pad5)") (class "Default")
      (node (ref "RN3") (pin "5") (pinfunction "5_5") (pintype "passive"))
    )
    (net (code "165") (name "unconnected-(RN3-Pad6)") (class "Default")
      (node (ref "RN3") (pin "6") (pinfunction "6_6") (pintype "passive"))
    )
    (net (code "166") (name "unconnected-(S2-Pad1)") (class "Default")
      (node (ref "S2") (pin "1") (pinfunction "1_1") (pintype "passive"))
    )
    (net (code "167") (name "{slash}CS_FM") (class "Default")
      (node (ref "IC3") (pin "7") (pinfunction "QH_7") (pintype "tri_state"))
      (node (ref "IC7") (pin "/CS") (pinfunction "/CS_/CS") (pintype "passive"))
    )
    (net (code "168") (name "{slash}CS_PSG") (class "Default")
      (node (ref "IC3") (pin "6") (pinfunction "QG_6") (pintype "tri_state"))
      (node (ref "IC8") (pin "/OE") (pinfunction "/OE_/OE") (pintype "passive"))
    )
    (net (code "169") (name "{slash}IC") (class "Default")
      (node (ref "IC3") (pin "4") (pinfunction "QE_4") (pintype "tri_state"))
      (node (ref "IC7") (pin "/IC") (pinfunction "/IC_/IC") (pintype "passive"))
    )
    (net (code "170") (name "{slash}WR") (class "Default")
      (node (ref "IC3") (pin "5") (pinfunction "QF_5") (pintype "tri_state"))
      (node (ref "IC7") (pin "/WR") (pinfunction "/WR_/WR") (pintype "passive"))
      (node (ref "IC8") (pin "/WE") (pinfunction "/WE_/WE") (pintype "passive"))
    )
  )
)
